# Mainboard.net
KiCad netlist of a schematic drawn in EAGLE
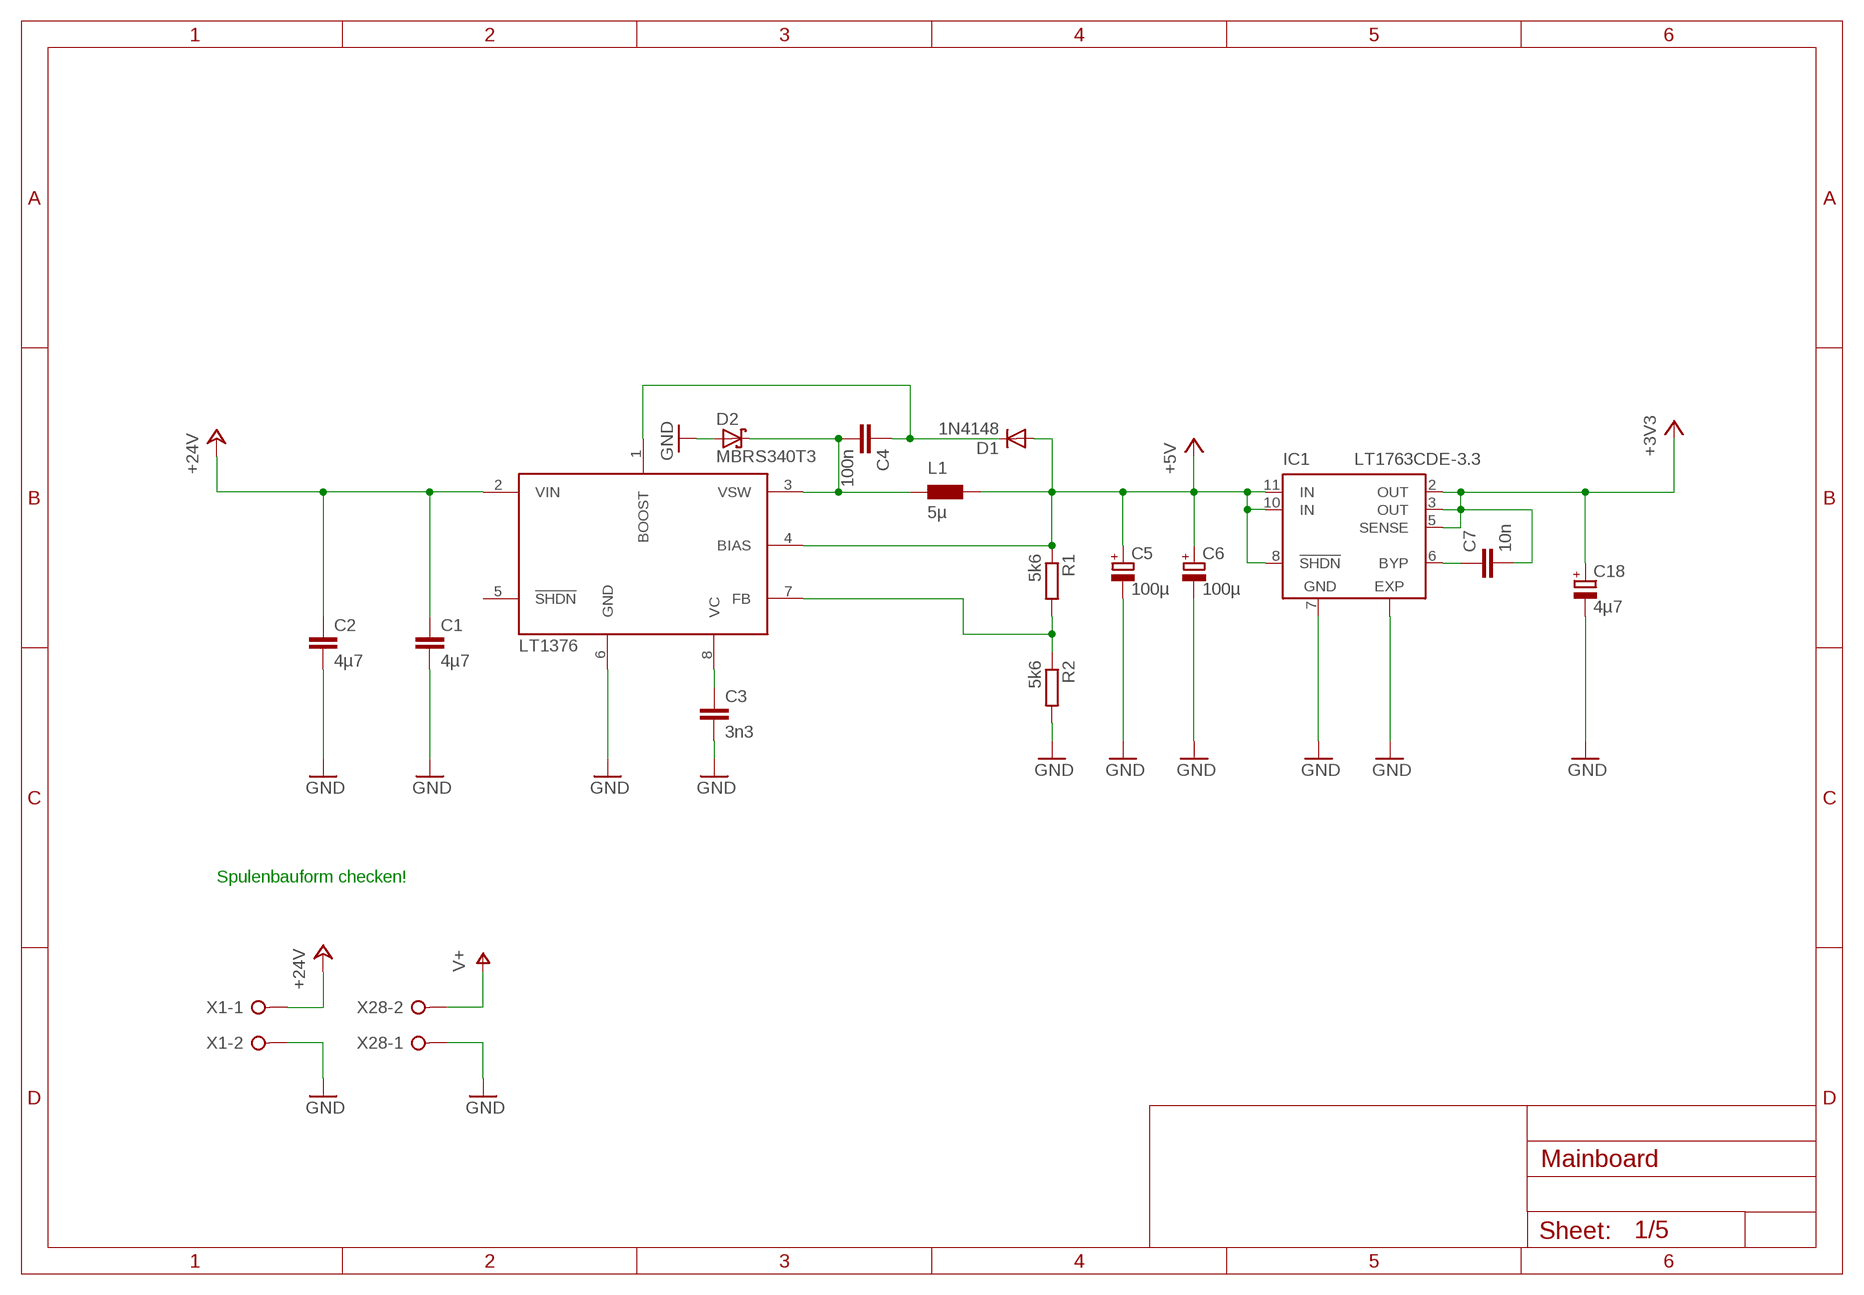
[diagram p0: schematic, sheet 1]
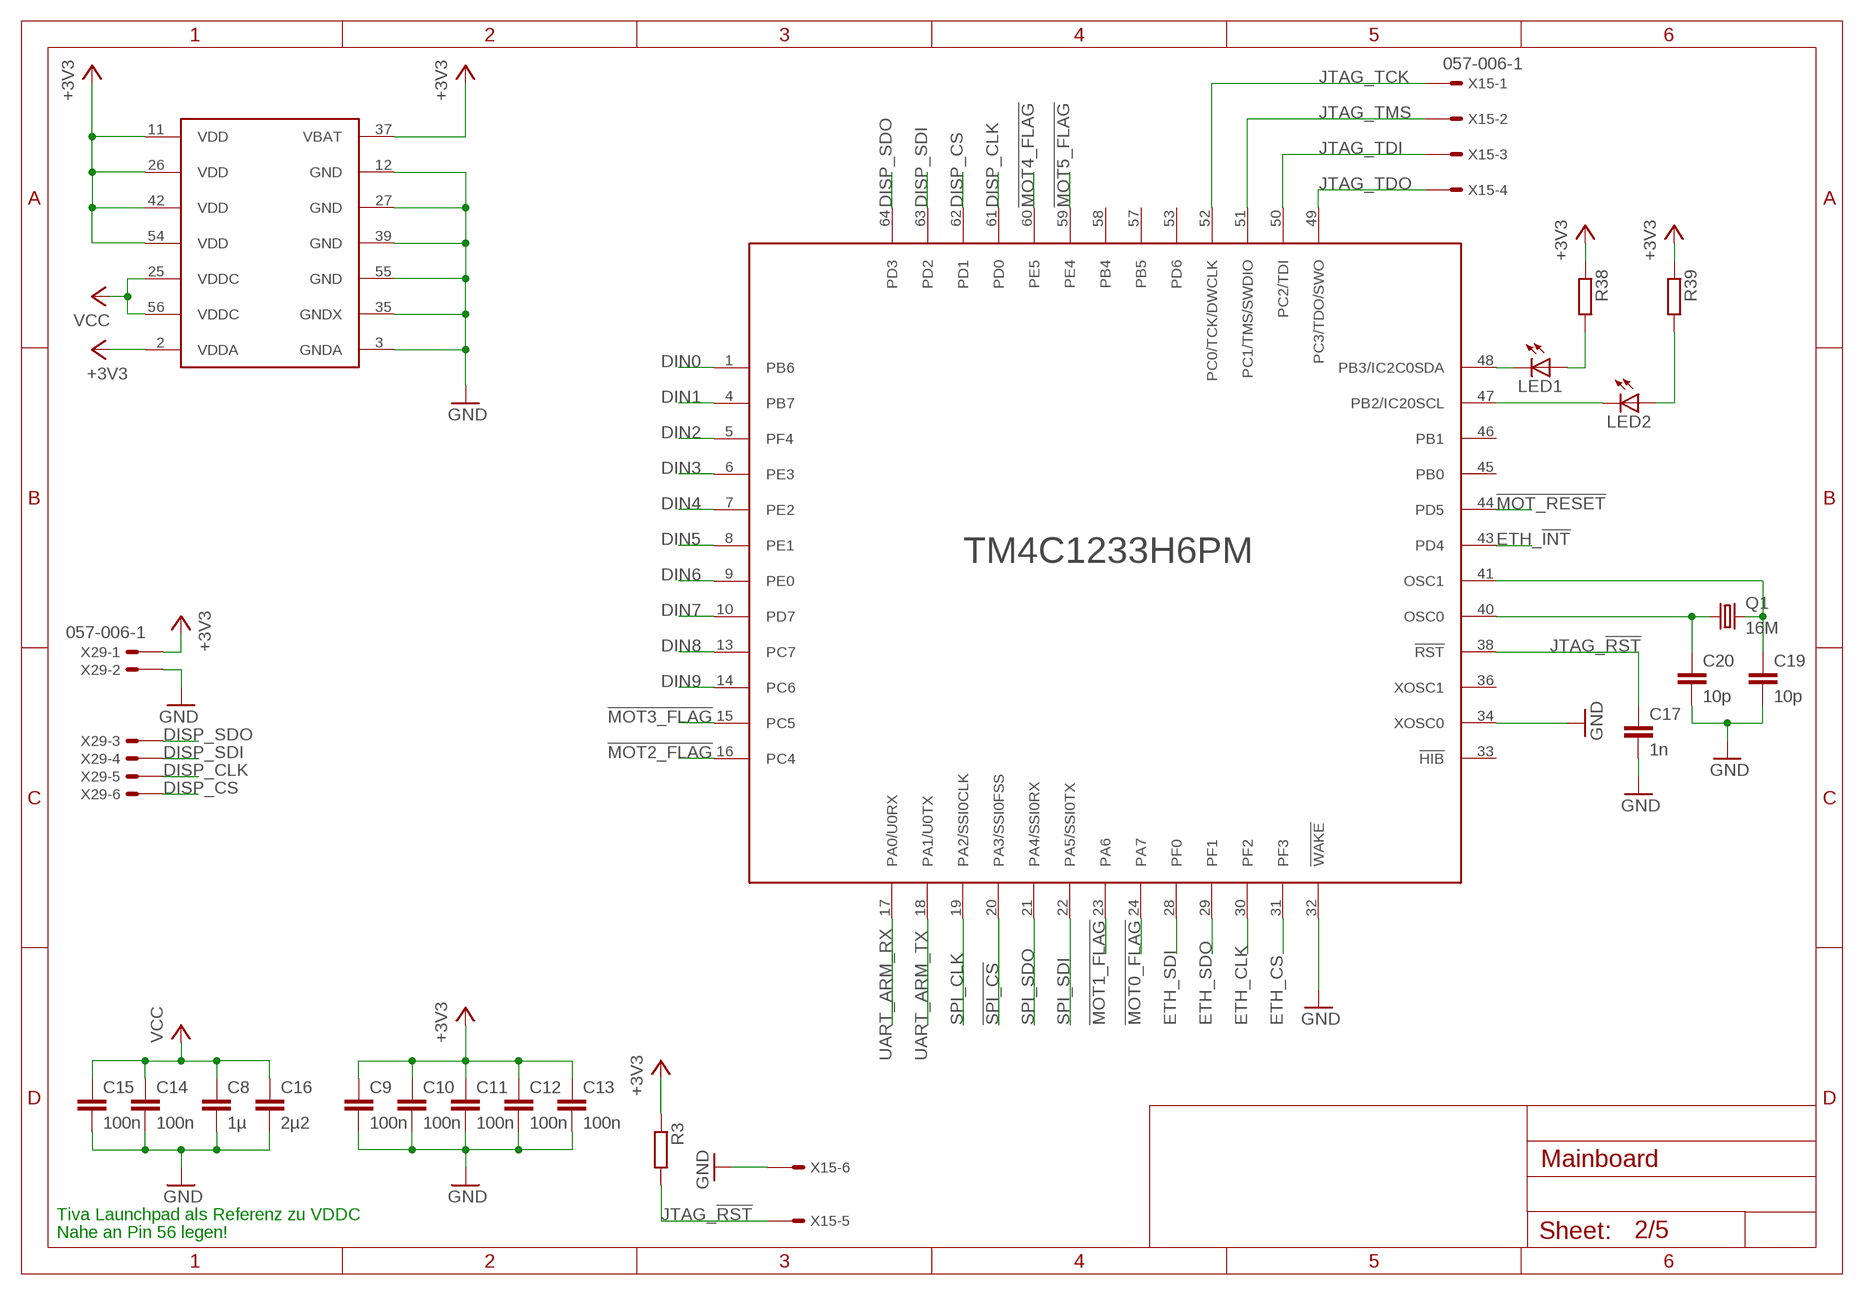
[diagram p1: schematic, sheet 2]
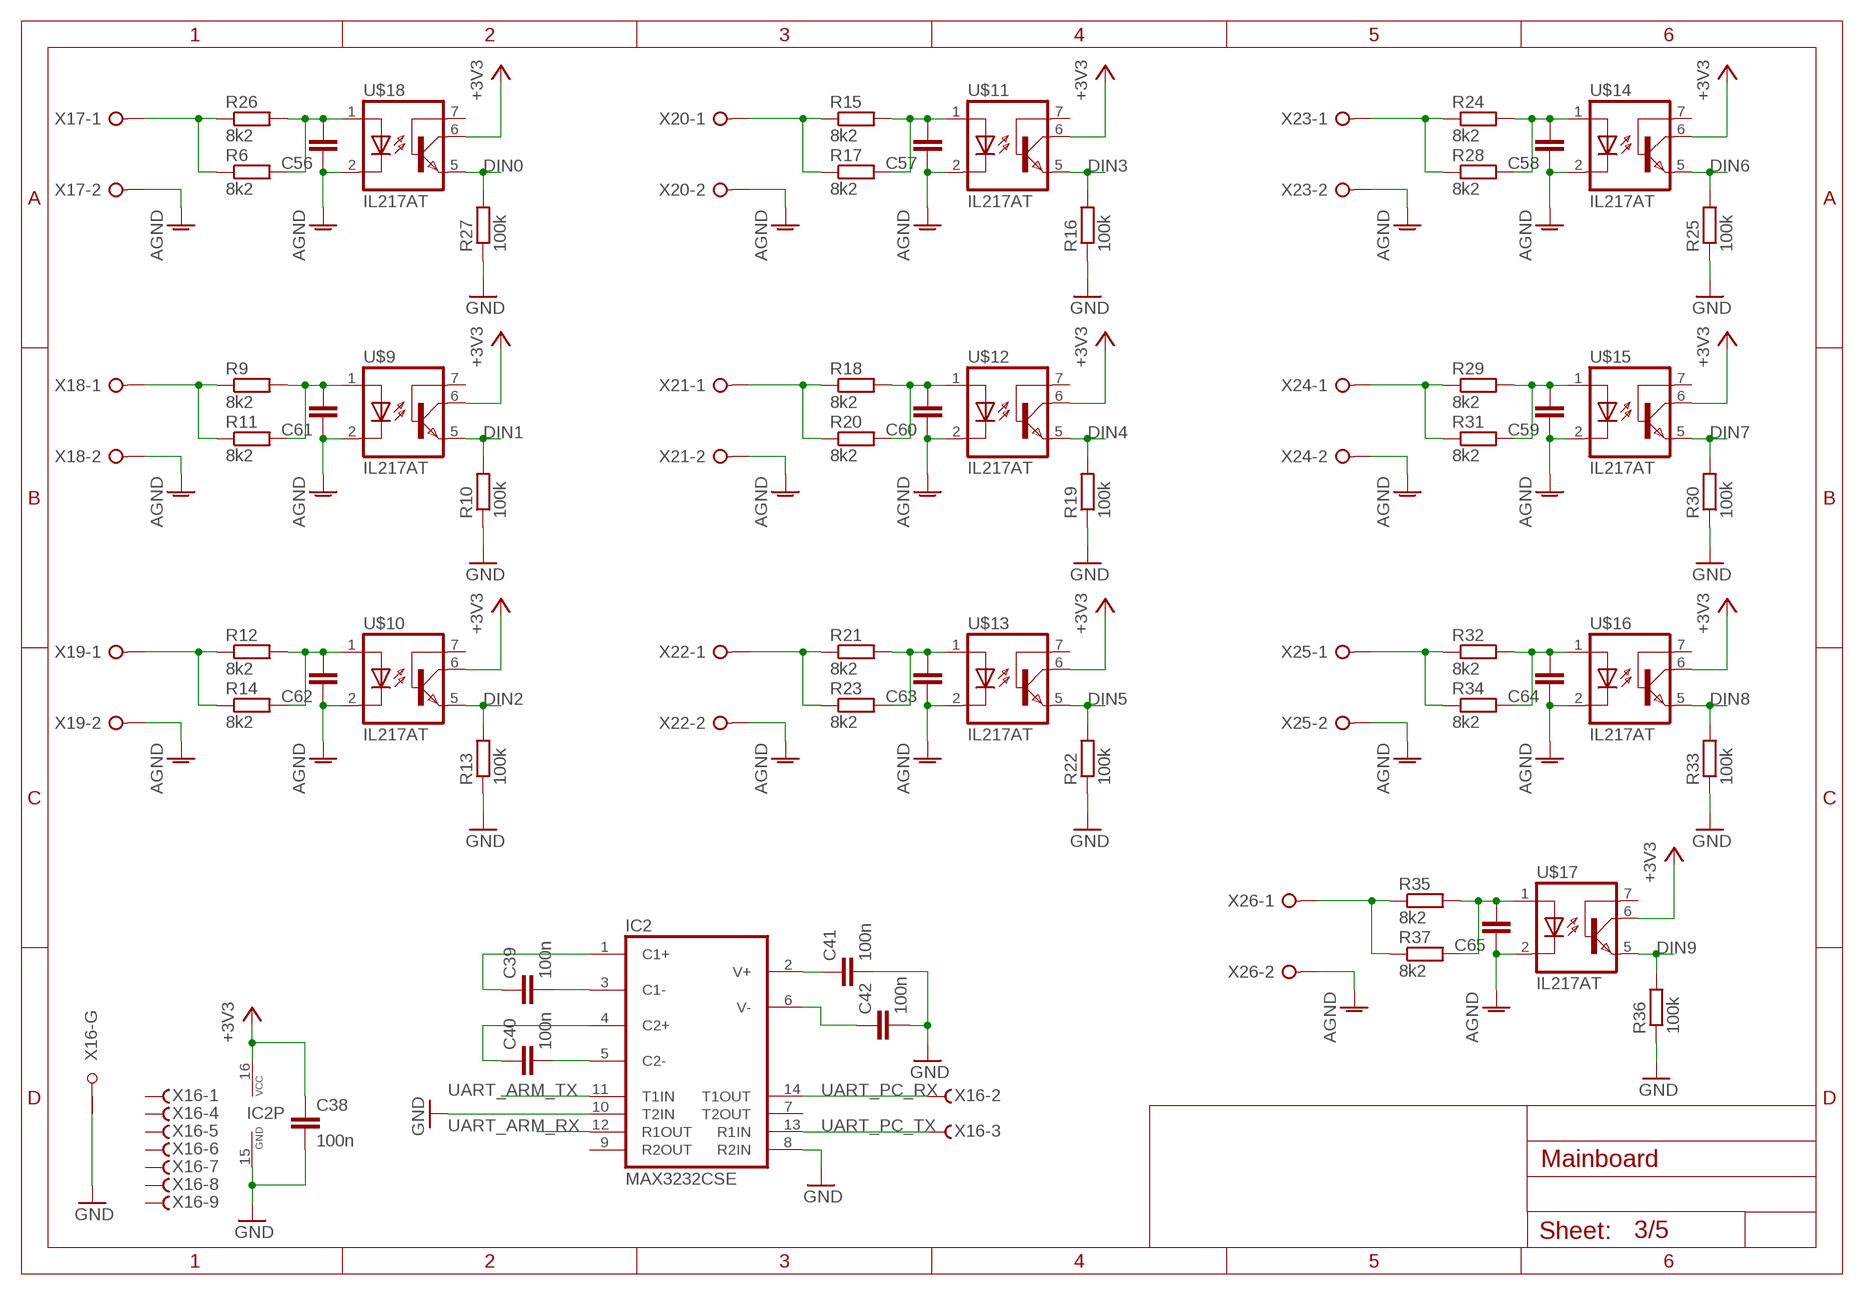
[diagram p2: schematic, sheet 3]
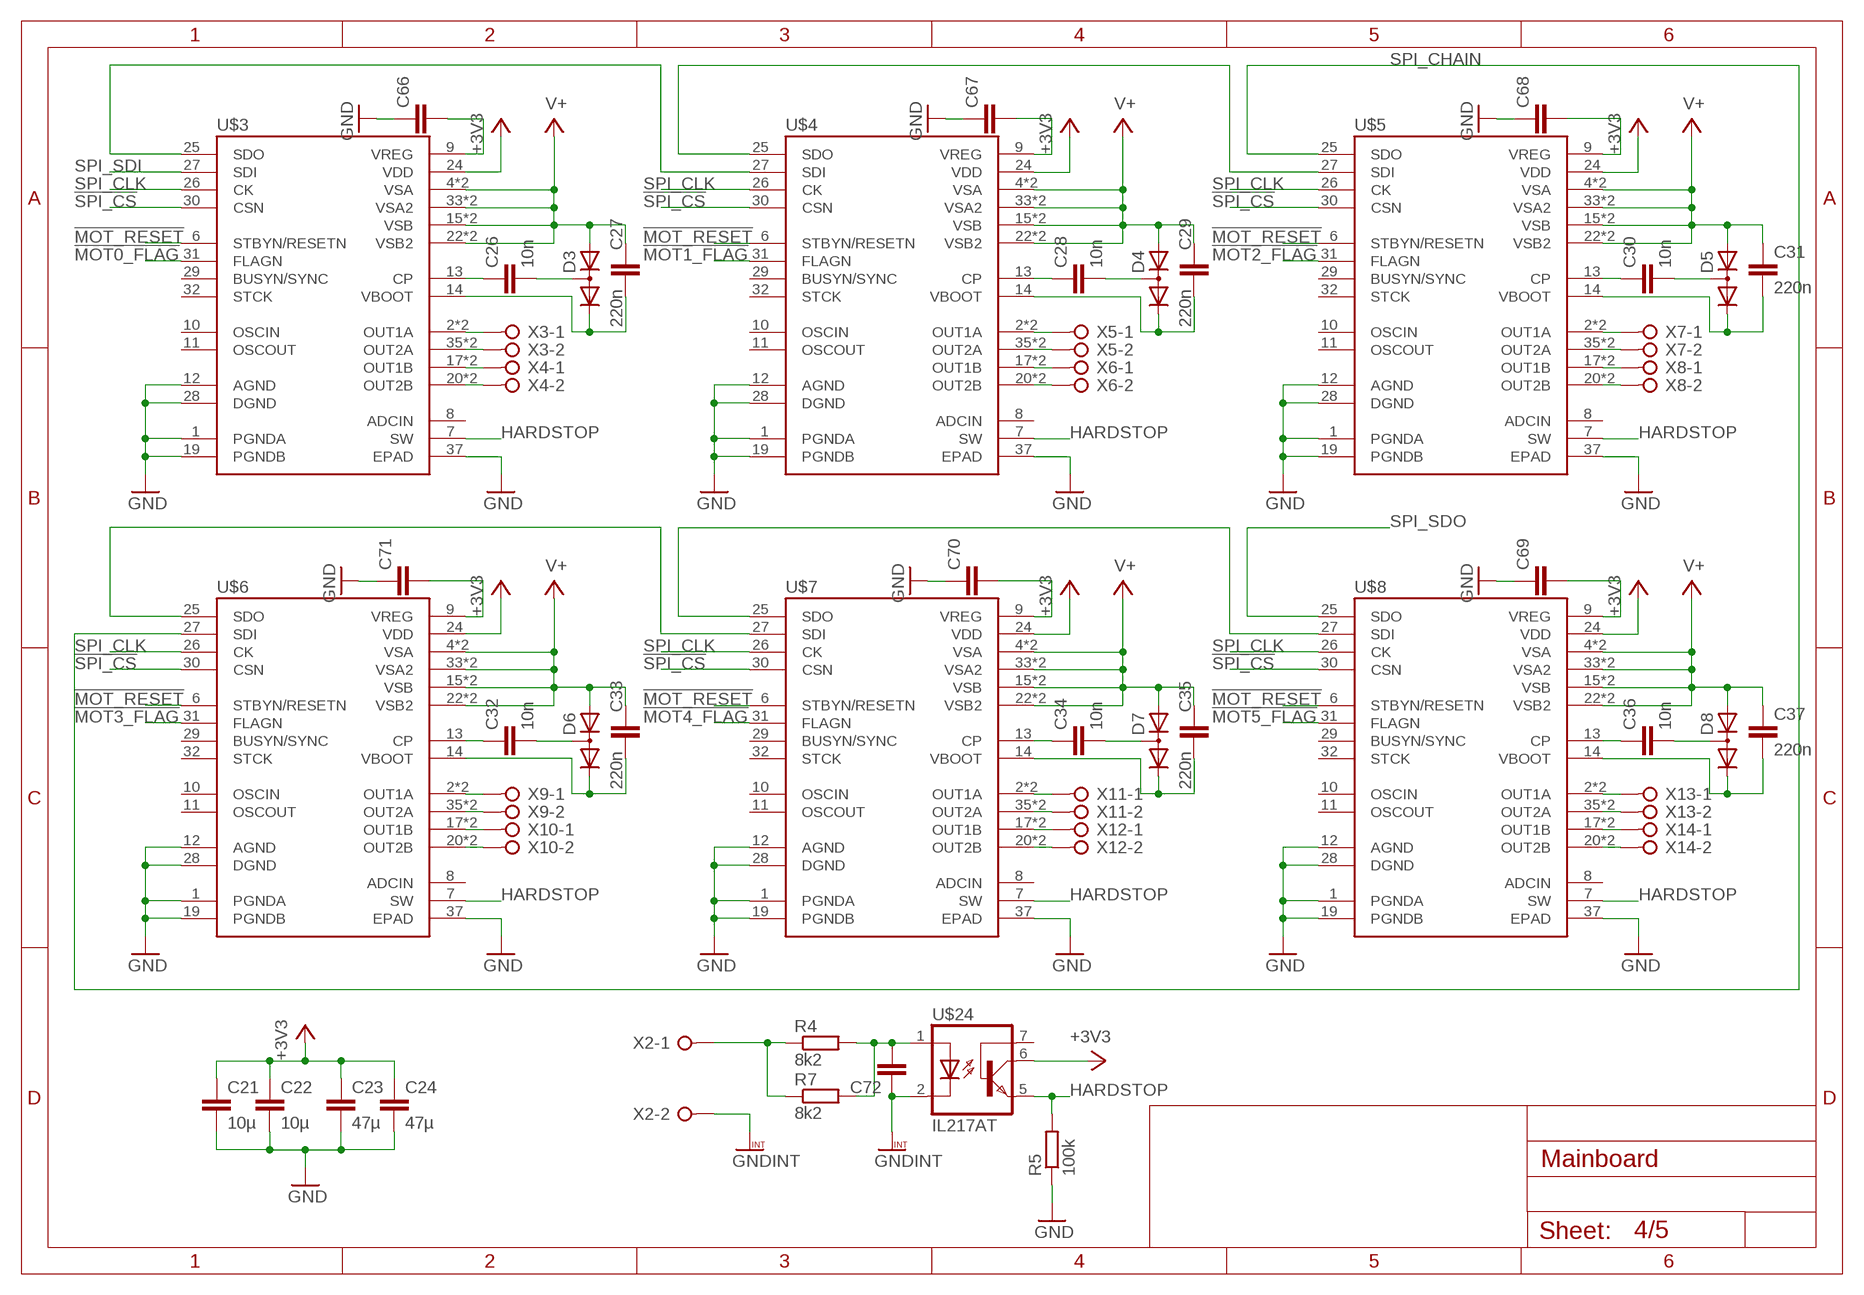
[diagram p3: schematic, sheet 4]
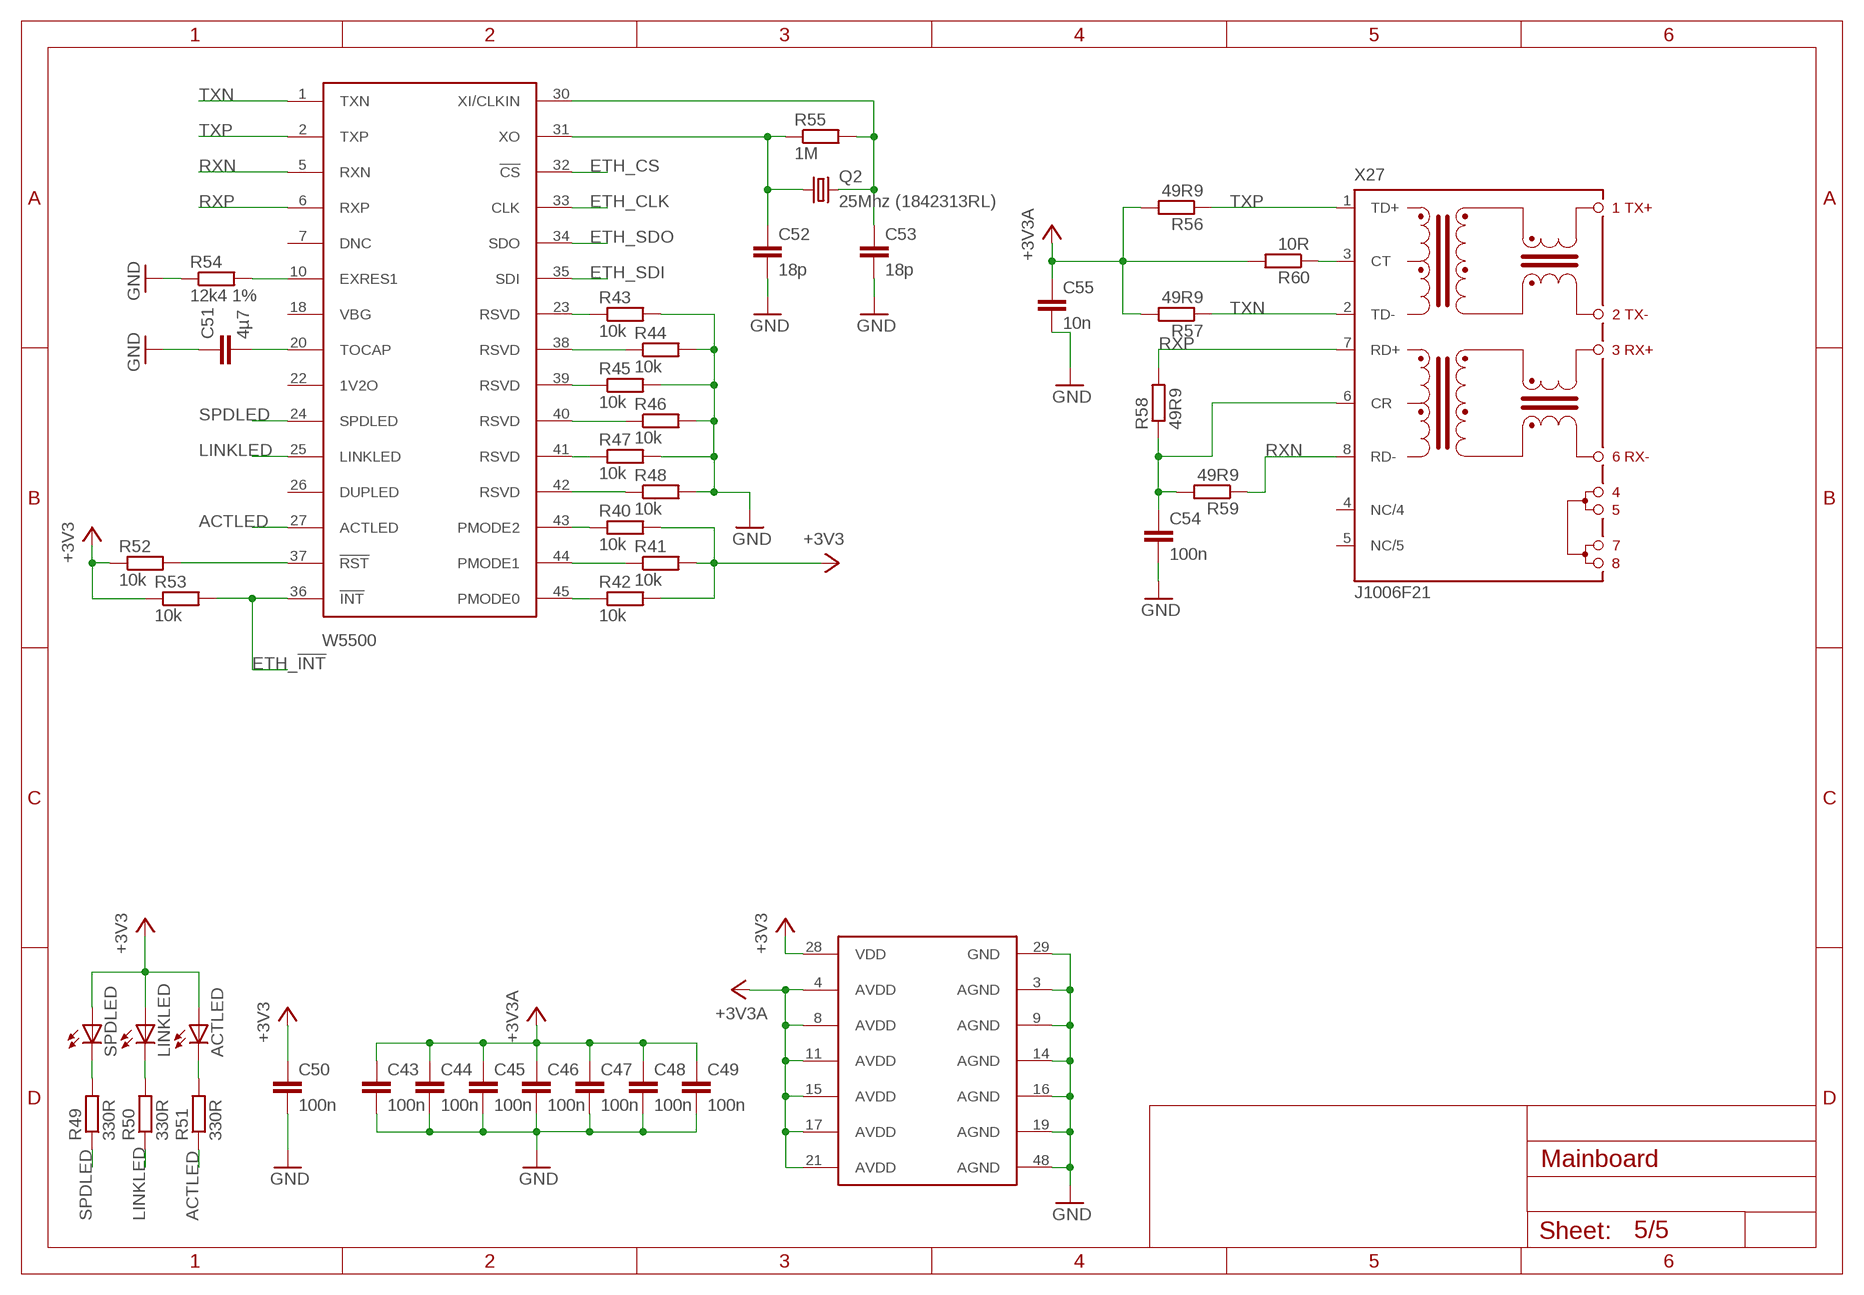
[diagram p4: schematic, sheet 5]

(export (version "E")
  (design (tool "Eeschema 10.0.6"))
  (components
    (comp (ref "ACTLED")
      (value "LEDCHIPLED_0805")
      (footprint "eagle-import:CHIPLED_0805")
      (libsource (lib "eagle-import") (part "LEDCHIPLED_0805"))
    )
    (comp (ref "C43")
      (value "100n")
      (footprint "eagle-import:C0805")
      (libsource (lib "eagle-import") (part "C-EUC0805"))
    )
    (comp (ref "C44")
      (value "100n")
      (footprint "eagle-import:C0805")
      (libsource (lib "eagle-import") (part "C-EUC0805"))
    )
    (comp (ref "C45")
      (value "100n")
      (footprint "eagle-import:C0805")
      (libsource (lib "eagle-import") (part "C-EUC0805"))
    )
    (comp (ref "C46")
      (value "100n")
      (footprint "eagle-import:C0805")
      (libsource (lib "eagle-import") (part "C-EUC0805"))
    )
    (comp (ref "C47")
      (value "100n")
      (footprint "eagle-import:C0805")
      (libsource (lib "eagle-import") (part "C-EUC0805"))
    )
    (comp (ref "C48")
      (value "100n")
      (footprint "eagle-import:C0805")
      (libsource (lib "eagle-import") (part "C-EUC0805"))
    )
    (comp (ref "C49")
      (value "100n")
      (footprint "eagle-import:C0805")
      (libsource (lib "eagle-import") (part "C-EUC0805"))
    )
    (comp (ref "C50")
      (value "100n")
      (footprint "eagle-import:C0805")
      (libsource (lib "eagle-import") (part "C-EUC0805"))
    )
    (comp (ref "C51")
      (value "4µ7")
      (footprint "eagle-import:C0805")
      (libsource (lib "eagle-import") (part "C-EUC0805"))
    )
    (comp (ref "C52")
      (value "18p")
      (footprint "eagle-import:C0805")
      (libsource (lib "eagle-import") (part "C-EUC0805"))
    )
    (comp (ref "C53")
      (value "18p")
      (footprint "eagle-import:C0805")
      (libsource (lib "eagle-import") (part "C-EUC0805"))
    )
    (comp (ref "C54")
      (value "100n")
      (footprint "eagle-import:C0805")
      (libsource (lib "eagle-import") (part "C-EUC0805"))
    )
    (comp (ref "C55")
      (value "10n")
      (footprint "eagle-import:C0805")
      (libsource (lib "eagle-import") (part "C-EUC0805"))
    )
    (comp (ref "LINKLED")
      (value "LEDCHIPLED_0805")
      (footprint "eagle-import:CHIPLED_0805")
      (libsource (lib "eagle-import") (part "LEDCHIPLED_0805"))
    )
    (comp (ref "Q2")
      (value "25Mhz (1842313RL)")
      (footprint "eagle-import:HC49UP")
      (libsource (lib "eagle-import") (part "CRYSTALHC49UP"))
    )
    (comp (ref "R40")
      (value "10k")
      (footprint "eagle-import:R0805")
      (libsource (lib "eagle-import") (part "R-EU_R0805"))
    )
    (comp (ref "R41")
      (value "10k")
      (footprint "eagle-import:R0805")
      (libsource (lib "eagle-import") (part "R-EU_R0805"))
    )
    (comp (ref "R42")
      (value "10k")
      (footprint "eagle-import:R0805")
      (libsource (lib "eagle-import") (part "R-EU_R0805"))
    )
    (comp (ref "R43")
      (value "10k")
      (footprint "eagle-import:R0805")
      (libsource (lib "eagle-import") (part "R-EU_R0805"))
    )
    (comp (ref "R44")
      (value "10k")
      (footprint "eagle-import:R0805")
      (libsource (lib "eagle-import") (part "R-EU_R0805"))
    )
    (comp (ref "R45")
      (value "10k")
      (footprint "eagle-import:R0805")
      (libsource (lib "eagle-import") (part "R-EU_R0805"))
    )
    (comp (ref "R46")
      (value "10k")
      (footprint "eagle-import:R0805")
      (libsource (lib "eagle-import") (part "R-EU_R0805"))
    )
    (comp (ref "R47")
      (value "10k")
      (footprint "eagle-import:R0805")
      (libsource (lib "eagle-import") (part "R-EU_R0805"))
    )
    (comp (ref "R48")
      (value "10k")
      (footprint "eagle-import:R0805")
      (libsource (lib "eagle-import") (part "R-EU_R0805"))
    )
    (comp (ref "R49")
      (value "330R")
      (footprint "eagle-import:R0805")
      (libsource (lib "eagle-import") (part "R-EU_R0805"))
    )
    (comp (ref "R50")
      (value "330R")
      (footprint "eagle-import:R0805")
      (libsource (lib "eagle-import") (part "R-EU_R0805"))
    )
    (comp (ref "R51")
      (value "330R")
      (footprint "eagle-import:R0805")
      (libsource (lib "eagle-import") (part "R-EU_R0805"))
    )
    (comp (ref "R52")
      (value "10k")
      (footprint "eagle-import:R0805")
      (libsource (lib "eagle-import") (part "R-EU_R0805"))
    )
    (comp (ref "R53")
      (value "10k")
      (footprint "eagle-import:R0805")
      (libsource (lib "eagle-import") (part "R-EU_R0805"))
    )
    (comp (ref "R54")
      (value "12k4 1%")
      (footprint "eagle-import:R0805")
      (libsource (lib "eagle-import") (part "R-EU_R0805"))
    )
    (comp (ref "R55")
      (value "1M")
      (footprint "eagle-import:R0805")
      (libsource (lib "eagle-import") (part "R-EU_R0805"))
    )
    (comp (ref "R56")
      (value "49R9")
      (footprint "eagle-import:R0805")
      (libsource (lib "eagle-import") (part "R-EU_R0805"))
    )
    (comp (ref "R57")
      (value "49R9")
      (footprint "eagle-import:R0805")
      (libsource (lib "eagle-import") (part "R-EU_R0805"))
    )
    (comp (ref "R58")
      (value "49R9")
      (footprint "eagle-import:R0805")
      (libsource (lib "eagle-import") (part "R-EU_R0805"))
    )
    (comp (ref "R59")
      (value "49R9")
      (footprint "eagle-import:R0805")
      (libsource (lib "eagle-import") (part "R-EU_R0805"))
    )
    (comp (ref "R60")
      (value "10R")
      (footprint "eagle-import:R0805")
      (libsource (lib "eagle-import") (part "R-EU_R0805"))
    )
    (comp (ref "SPDLED")
      (value "LEDCHIPLED_0805")
      (footprint "eagle-import:CHIPLED_0805")
      (libsource (lib "eagle-import") (part "LEDCHIPLED_0805"))
    )
    (comp (ref "U$19")
      (value "W5500")
      (footprint "eagle-import:LQFP48")
      (libsource (lib "eagle-import") (part "W5500"))
    )
    (comp (ref "X27")
      (value "J1006F21")
      (footprint "eagle-import:J1")
      (libsource (lib "eagle-import") (part "J1006F21"))
    )
    (comp (ref "C21")
      (value "10µ")
      (footprint "eagle-import:C0805")
      (libsource (lib "eagle-import") (part "C-EUC0805"))
    )
    (comp (ref "C22")
      (value "10µ")
      (footprint "eagle-import:C0805")
      (libsource (lib "eagle-import") (part "C-EUC0805"))
    )
    (comp (ref "C23")
      (value "47µ")
      (footprint "eagle-import:C0805")
      (libsource (lib "eagle-import") (part "C-EUC0805"))
    )
    (comp (ref "C24")
      (value "47µ")
      (footprint "eagle-import:C0805")
      (libsource (lib "eagle-import") (part "C-EUC0805"))
    )
    (comp (ref "C26")
      (value "10n")
      (footprint "eagle-import:C0805")
      (libsource (lib "eagle-import") (part "C-EUC0805"))
    )
    (comp (ref "C27")
      (value "220n")
      (footprint "eagle-import:C0805")
      (libsource (lib "eagle-import") (part "C-EUC0805"))
    )
    (comp (ref "C28")
      (value "10n")
      (footprint "eagle-import:C0805")
      (libsource (lib "eagle-import") (part "C-EUC0805"))
    )
    (comp (ref "C29")
      (value "220n")
      (footprint "eagle-import:C0805")
      (libsource (lib "eagle-import") (part "C-EUC0805"))
    )
    (comp (ref "C30")
      (value "10n")
      (footprint "eagle-import:C0805")
      (libsource (lib "eagle-import") (part "C-EUC0805"))
    )
    (comp (ref "C31")
      (value "220n")
      (footprint "eagle-import:C0805")
      (libsource (lib "eagle-import") (part "C-EUC0805"))
    )
    (comp (ref "C32")
      (value "10n")
      (footprint "eagle-import:C0805")
      (libsource (lib "eagle-import") (part "C-EUC0805"))
    )
    (comp (ref "C33")
      (value "220n")
      (footprint "eagle-import:C0805")
      (libsource (lib "eagle-import") (part "C-EUC0805"))
    )
    (comp (ref "C34")
      (value "10n")
      (footprint "eagle-import:C0805")
      (libsource (lib "eagle-import") (part "C-EUC0805"))
    )
    (comp (ref "C35")
      (value "220n")
      (footprint "eagle-import:C0805")
      (libsource (lib "eagle-import") (part "C-EUC0805"))
    )
    (comp (ref "C36")
      (value "10n")
      (footprint "eagle-import:C0805")
      (libsource (lib "eagle-import") (part "C-EUC0805"))
    )
    (comp (ref "C37")
      (value "220n")
      (footprint "eagle-import:C0805")
      (libsource (lib "eagle-import") (part "C-EUC0805"))
    )
    (comp (ref "C66")
      (value "C-EUC1210")
      (footprint "eagle-import:C1210")
      (libsource (lib "eagle-import") (part "C-EUC1210"))
    )
    (comp (ref "C67")
      (value "C-EUC1210")
      (footprint "eagle-import:C1210")
      (libsource (lib "eagle-import") (part "C-EUC1210"))
    )
    (comp (ref "C68")
      (value "C-EUC1210")
      (footprint "eagle-import:C1210")
      (libsource (lib "eagle-import") (part "C-EUC1210"))
    )
    (comp (ref "C69")
      (value "C-EUC1210")
      (footprint "eagle-import:C1210")
      (libsource (lib "eagle-import") (part "C-EUC1210"))
    )
    (comp (ref "C70")
      (value "C-EUC1210")
      (footprint "eagle-import:C1210")
      (libsource (lib "eagle-import") (part "C-EUC1210"))
    )
    (comp (ref "C71")
      (value "C-EUC1210")
      (footprint "eagle-import:C1210")
      (libsource (lib "eagle-import") (part "C-EUC1210"))
    )
    (comp (ref "C72")
      (value "C-EUC1210")
      (footprint "eagle-import:C1210")
      (libsource (lib "eagle-import") (part "C-EUC1210"))
    )
    (comp (ref "D3")
      (value "HSMS-2802-TR1G")
      (footprint "eagle-import:SOT23")
      (libsource (lib "eagle-import") (part "DIODE_2CACA-SOT23"))
    )
    (comp (ref "D4")
      (value "HSMS-2802-TR1G")
      (footprint "eagle-import:SOT23")
      (libsource (lib "eagle-import") (part "DIODE_2CACA-SOT23"))
    )
    (comp (ref "D5")
      (value "HSMS-2802-TR1G")
      (footprint "eagle-import:SOT23")
      (libsource (lib "eagle-import") (part "DIODE_2CACA-SOT23"))
    )
    (comp (ref "D6")
      (value "HSMS-2802-TR1G")
      (footprint "eagle-import:SOT23")
      (libsource (lib "eagle-import") (part "DIODE_2CACA-SOT23"))
    )
    (comp (ref "D7")
      (value "HSMS-2802-TR1G")
      (footprint "eagle-import:SOT23")
      (libsource (lib "eagle-import") (part "DIODE_2CACA-SOT23"))
    )
    (comp (ref "D8")
      (value "HSMS-2802-TR1G")
      (footprint "eagle-import:SOT23")
      (libsource (lib "eagle-import") (part "DIODE_2CACA-SOT23"))
    )
    (comp (ref "R4")
      (value "8k2")
      (footprint "eagle-import:R0805")
      (libsource (lib "eagle-import") (part "R-EU_R0805"))
    )
    (comp (ref "R5")
      (value "100k")
      (footprint "eagle-import:R0805")
      (libsource (lib "eagle-import") (part "R-EU_R0805"))
    )
    (comp (ref "R7")
      (value "8k2")
      (footprint "eagle-import:R0805")
      (libsource (lib "eagle-import") (part "R-EU_R0805"))
    )
    (comp (ref "U$3")
      (value "L6470HPOWERSO36")
      (footprint "eagle-import:SOP65P1400X360-37N")
      (libsource (lib "eagle-import") (part "L6470HPOWERSO36"))
    )
    (comp (ref "U$4")
      (value "L6470HPOWERSO36")
      (footprint "eagle-import:SOP65P1400X360-37N")
      (libsource (lib "eagle-import") (part "L6470HPOWERSO36"))
    )
    (comp (ref "U$5")
      (value "L6470HPOWERSO36")
      (footprint "eagle-import:SOP65P1400X360-37N")
      (libsource (lib "eagle-import") (part "L6470HPOWERSO36"))
    )
    (comp (ref "U$6")
      (value "L6470HPOWERSO36")
      (footprint "eagle-import:SOP65P1400X360-37N")
      (libsource (lib "eagle-import") (part "L6470HPOWERSO36"))
    )
    (comp (ref "U$7")
      (value "L6470HPOWERSO36")
      (footprint "eagle-import:SOP65P1400X360-37N")
      (libsource (lib "eagle-import") (part "L6470HPOWERSO36"))
    )
    (comp (ref "U$8")
      (value "L6470HPOWERSO36")
      (footprint "eagle-import:SOP65P1400X360-37N")
      (libsource (lib "eagle-import") (part "L6470HPOWERSO36"))
    )
    (comp (ref "U$24")
      (value "IL217AT")
      (footprint "eagle-import:SOIC8")
      (libsource (lib "eagle-import") (part "IL217AT"))
    )
    (comp (ref "X2")
      (value "W237-02P")
      (footprint "eagle-import:W237-132")
      (libsource (lib "eagle-import") (part "W237-02P"))
    )
    (comp (ref "X3")
      (value "W237-02P")
      (footprint "eagle-import:W237-132")
      (libsource (lib "eagle-import") (part "W237-02P"))
    )
    (comp (ref "X4")
      (value "W237-02P")
      (footprint "eagle-import:W237-132")
      (libsource (lib "eagle-import") (part "W237-02P"))
    )
    (comp (ref "X5")
      (value "W237-02P")
      (footprint "eagle-import:W237-132")
      (libsource (lib "eagle-import") (part "W237-02P"))
    )
    (comp (ref "X6")
      (value "W237-02P")
      (footprint "eagle-import:W237-132")
      (libsource (lib "eagle-import") (part "W237-02P"))
    )
    (comp (ref "X7")
      (value "W237-02P")
      (footprint "eagle-import:W237-132")
      (libsource (lib "eagle-import") (part "W237-02P"))
    )
    (comp (ref "X8")
      (value "W237-02P")
      (footprint "eagle-import:W237-132")
      (libsource (lib "eagle-import") (part "W237-02P"))
    )
    (comp (ref "X9")
      (value "W237-02P")
      (footprint "eagle-import:W237-132")
      (libsource (lib "eagle-import") (part "W237-02P"))
    )
    (comp (ref "X10")
      (value "W237-02P")
      (footprint "eagle-import:W237-132")
      (libsource (lib "eagle-import") (part "W237-02P"))
    )
    (comp (ref "X11")
      (value "W237-02P")
      (footprint "eagle-import:W237-132")
      (libsource (lib "eagle-import") (part "W237-02P"))
    )
    (comp (ref "X12")
      (value "W237-02P")
      (footprint "eagle-import:W237-132")
      (libsource (lib "eagle-import") (part "W237-02P"))
    )
    (comp (ref "X13")
      (value "W237-02P")
      (footprint "eagle-import:W237-132")
      (libsource (lib "eagle-import") (part "W237-02P"))
    )
    (comp (ref "X14")
      (value "W237-02P")
      (footprint "eagle-import:W237-132")
      (libsource (lib "eagle-import") (part "W237-02P"))
    )
    (comp (ref "C1")
      (value "4µ7")
      (footprint "eagle-import:C0805")
      (libsource (lib "eagle-import") (part "C-EUC0805"))
    )
    (comp (ref "C2")
      (value "4µ7")
      (footprint "eagle-import:C0805")
      (libsource (lib "eagle-import") (part "C-EUC0805"))
    )
    (comp (ref "C3")
      (value "3n3")
      (footprint "eagle-import:C0805")
      (libsource (lib "eagle-import") (part "C-EUC0805"))
    )
    (comp (ref "C4")
      (value "100n")
      (footprint "eagle-import:C0805")
      (libsource (lib "eagle-import") (part "C-EUC0805"))
    )
    (comp (ref "C5")
      (value "100µ")
      (footprint "eagle-import:UD-6,3X7,7_NICHICON")
      (libsource (lib "eagle-import") (part "CPOL-EUUD-6,3X7,7"))
    )
    (comp (ref "C6")
      (value "100µ")
      (footprint "eagle-import:UD-6,3X7,7_NICHICON")
      (libsource (lib "eagle-import") (part "CPOL-EUUD-6,3X7,7"))
    )
    (comp (ref "C7")
      (value "10n")
      (footprint "eagle-import:C0805")
      (libsource (lib "eagle-import") (part "C-EUC0805"))
    )
    (comp (ref "C18")
      (value "4µ7")
      (footprint "eagle-import:UD-6,3X7,7_NICHICON")
      (libsource (lib "eagle-import") (part "CPOL-EUUD-6,3X7,7"))
    )
    (comp (ref "D1")
      (value "1N4148")
      (footprint "eagle-import:SOD123")
      (libsource (lib "eagle-import") (part "DIODE-SOD123"))
    )
    (comp (ref "D2")
      (value "MBRS340T3")
      (footprint "eagle-import:SMC")
      (libsource (lib "eagle-import") (part "MBRS30T34"))
    )
    (comp (ref "IC1")
      (value "LT1763CDE-3.3")
      (footprint "eagle-import:DFN12")
      (libsource (lib "eagle-import") (part "LT1763CDE-3.3"))
    )
    (comp (ref "L1")
      (value "5µ")
      (footprint "eagle-import:PIS4720")
      (libsource (lib "eagle-import") (part "PIS4720"))
    )
    (comp (ref "R1")
      (value "5k6")
      (footprint "eagle-import:R0805")
      (libsource (lib "eagle-import") (part "R-EU_R0805"))
    )
    (comp (ref "R2")
      (value "5k6")
      (footprint "eagle-import:R0805")
      (libsource (lib "eagle-import") (part "R-EU_R0805"))
    )
    (comp (ref "U$1")
      (value "LT1376")
      (footprint "eagle-import:SOIC8")
      (libsource (lib "eagle-import") (part "LT1376"))
    )
    (comp (ref "X1")
      (value "W237-02P")
      (footprint "eagle-import:W237-132")
      (libsource (lib "eagle-import") (part "W237-02P"))
    )
    (comp (ref "X28")
      (value "W237-02P")
      (footprint "eagle-import:W237-132")
      (fields (field (name "OC_FARNELL") "unknown") (field (name "OC_NEWARK") "unknown"))
      (libsource (lib "eagle-import") (part "W237-02P"))
    )
    (comp (ref "C38")
      (value "100n")
      (footprint "eagle-import:C0805")
      (libsource (lib "eagle-import") (part "C-EUC0805"))
    )
    (comp (ref "C39")
      (value "100n")
      (footprint "eagle-import:C0805")
      (libsource (lib "eagle-import") (part "C-EUC0805"))
    )
    (comp (ref "C40")
      (value "100n")
      (footprint "eagle-import:C0805")
      (libsource (lib "eagle-import") (part "C-EUC0805"))
    )
    (comp (ref "C41")
      (value "100n")
      (footprint "eagle-import:C0805")
      (libsource (lib "eagle-import") (part "C-EUC0805"))
    )
    (comp (ref "C42")
      (value "100n")
      (footprint "eagle-import:C0805")
      (libsource (lib "eagle-import") (part "C-EUC0805"))
    )
    (comp (ref "C56")
      (value "C-EUC1210")
      (footprint "eagle-import:C1210")
      (libsource (lib "eagle-import") (part "C-EUC1210"))
    )
    (comp (ref "C57")
      (value "C-EUC1210")
      (footprint "eagle-import:C1210")
      (libsource (lib "eagle-import") (part "C-EUC1210"))
    )
    (comp (ref "C58")
      (value "C-EUC1210")
      (footprint "eagle-import:C1210")
      (libsource (lib "eagle-import") (part "C-EUC1210"))
    )
    (comp (ref "C59")
      (value "C-EUC1210")
      (footprint "eagle-import:C1210")
      (libsource (lib "eagle-import") (part "C-EUC1210"))
    )
    (comp (ref "C60")
      (value "C-EUC1210")
      (footprint "eagle-import:C1210")
      (libsource (lib "eagle-import") (part "C-EUC1210"))
    )
    (comp (ref "C61")
      (value "C-EUC1210")
      (footprint "eagle-import:C1210")
      (libsource (lib "eagle-import") (part "C-EUC1210"))
    )
    (comp (ref "C62")
      (value "C-EUC1210")
      (footprint "eagle-import:C1210")
      (libsource (lib "eagle-import") (part "C-EUC1210"))
    )
    (comp (ref "C63")
      (value "C-EUC1210")
      (footprint "eagle-import:C1210")
      (libsource (lib "eagle-import") (part "C-EUC1210"))
    )
    (comp (ref "C64")
      (value "C-EUC1210")
      (footprint "eagle-import:C1210")
      (libsource (lib "eagle-import") (part "C-EUC1210"))
    )
    (comp (ref "C65")
      (value "C-EUC1210")
      (footprint "eagle-import:C1210")
      (libsource (lib "eagle-import") (part "C-EUC1210"))
    )
    (comp (ref "IC2")
      (value "MAX3232CSE")
      (footprint "eagle-import:SO16")
      (libsource (lib "eagle-import") (part "MAX3232SEC"))
    )
    (comp (ref "R6")
      (value "8k2")
      (footprint "eagle-import:R0805")
      (libsource (lib "eagle-import") (part "R-EU_R0805"))
    )
    (comp (ref "R9")
      (value "8k2")
      (footprint "eagle-import:R0805")
      (libsource (lib "eagle-import") (part "R-EU_R0805"))
    )
    (comp (ref "R10")
      (value "100k")
      (footprint "eagle-import:R0805")
      (libsource (lib "eagle-import") (part "R-EU_R0805"))
    )
    (comp (ref "R11")
      (value "8k2")
      (footprint "eagle-import:R0805")
      (libsource (lib "eagle-import") (part "R-EU_R0805"))
    )
    (comp (ref "R12")
      (value "8k2")
      (footprint "eagle-import:R0805")
      (libsource (lib "eagle-import") (part "R-EU_R0805"))
    )
    (comp (ref "R13")
      (value "100k")
      (footprint "eagle-import:R0805")
      (libsource (lib "eagle-import") (part "R-EU_R0805"))
    )
    (comp (ref "R14")
      (value "8k2")
      (footprint "eagle-import:R0805")
      (libsource (lib "eagle-import") (part "R-EU_R0805"))
    )
    (comp (ref "R15")
      (value "8k2")
      (footprint "eagle-import:R0805")
      (libsource (lib "eagle-import") (part "R-EU_R0805"))
    )
    (comp (ref "R16")
      (value "100k")
      (footprint "eagle-import:R0805")
      (libsource (lib "eagle-import") (part "R-EU_R0805"))
    )
    (comp (ref "R17")
      (value "8k2")
      (footprint "eagle-import:R0805")
      (libsource (lib "eagle-import") (part "R-EU_R0805"))
    )
    (comp (ref "R18")
      (value "8k2")
      (footprint "eagle-import:R0805")
      (libsource (lib "eagle-import") (part "R-EU_R0805"))
    )
    (comp (ref "R19")
      (value "100k")
      (footprint "eagle-import:R0805")
      (libsource (lib "eagle-import") (part "R-EU_R0805"))
    )
    (comp (ref "R20")
      (value "8k2")
      (footprint "eagle-import:R0805")
      (libsource (lib "eagle-import") (part "R-EU_R0805"))
    )
    (comp (ref "R21")
      (value "8k2")
      (footprint "eagle-import:R0805")
      (libsource (lib "eagle-import") (part "R-EU_R0805"))
    )
    (comp (ref "R22")
      (value "100k")
      (footprint "eagle-import:R0805")
      (libsource (lib "eagle-import") (part "R-EU_R0805"))
    )
    (comp (ref "R23")
      (value "8k2")
      (footprint "eagle-import:R0805")
      (libsource (lib "eagle-import") (part "R-EU_R0805"))
    )
    (comp (ref "R24")
      (value "8k2")
      (footprint "eagle-import:R0805")
      (libsource (lib "eagle-import") (part "R-EU_R0805"))
    )
    (comp (ref "R25")
      (value "100k")
      (footprint "eagle-import:R0805")
      (libsource (lib "eagle-import") (part "R-EU_R0805"))
    )
    (comp (ref "R26")
      (value "8k2")
      (footprint "eagle-import:R0805")
      (libsource (lib "eagle-import") (part "R-EU_R0805"))
    )
    (comp (ref "R27")
      (value "100k")
      (footprint "eagle-import:R0805")
      (libsource (lib "eagle-import") (part "R-EU_R0805"))
    )
    (comp (ref "R28")
      (value "8k2")
      (footprint "eagle-import:R0805")
      (libsource (lib "eagle-import") (part "R-EU_R0805"))
    )
    (comp (ref "R29")
      (value "8k2")
      (footprint "eagle-import:R0805")
      (libsource (lib "eagle-import") (part "R-EU_R0805"))
    )
    (comp (ref "R30")
      (value "100k")
      (footprint "eagle-import:R0805")
      (libsource (lib "eagle-import") (part "R-EU_R0805"))
    )
    (comp (ref "R31")
      (value "8k2")
      (footprint "eagle-import:R0805")
      (libsource (lib "eagle-import") (part "R-EU_R0805"))
    )
    (comp (ref "R32")
      (value "8k2")
      (footprint "eagle-import:R0805")
      (libsource (lib "eagle-import") (part "R-EU_R0805"))
    )
    (comp (ref "R33")
      (value "100k")
      (footprint "eagle-import:R0805")
      (libsource (lib "eagle-import") (part "R-EU_R0805"))
    )
    (comp (ref "R34")
      (value "8k2")
      (footprint "eagle-import:R0805")
      (libsource (lib "eagle-import") (part "R-EU_R0805"))
    )
    (comp (ref "R35")
      (value "8k2")
      (footprint "eagle-import:R0805")
      (libsource (lib "eagle-import") (part "R-EU_R0805"))
    )
    (comp (ref "R36")
      (value "100k")
      (footprint "eagle-import:R0805")
      (libsource (lib "eagle-import") (part "R-EU_R0805"))
    )
    (comp (ref "R37")
      (value "8k2")
      (footprint "eagle-import:R0805")
      (libsource (lib "eagle-import") (part "R-EU_R0805"))
    )
    (comp (ref "U$9")
      (value "IL217AT")
      (footprint "eagle-import:SOIC8")
      (libsource (lib "eagle-import") (part "IL217AT"))
    )
    (comp (ref "U$10")
      (value "IL217AT")
      (footprint "eagle-import:SOIC8")
      (libsource (lib "eagle-import") (part "IL217AT"))
    )
    (comp (ref "U$11")
      (value "IL217AT")
      (footprint "eagle-import:SOIC8")
      (libsource (lib "eagle-import") (part "IL217AT"))
    )
    (comp (ref "U$12")
      (value "IL217AT")
      (footprint "eagle-import:SOIC8")
      (libsource (lib "eagle-import") (part "IL217AT"))
    )
    (comp (ref "U$13")
      (value "IL217AT")
      (footprint "eagle-import:SOIC8")
      (libsource (lib "eagle-import") (part "IL217AT"))
    )
    (comp (ref "U$14")
      (value "IL217AT")
      (footprint "eagle-import:SOIC8")
      (libsource (lib "eagle-import") (part "IL217AT"))
    )
    (comp (ref "U$15")
      (value "IL217AT")
      (footprint "eagle-import:SOIC8")
      (libsource (lib "eagle-import") (part "IL217AT"))
    )
    (comp (ref "U$16")
      (value "IL217AT")
      (footprint "eagle-import:SOIC8")
      (libsource (lib "eagle-import") (part "IL217AT"))
    )
    (comp (ref "U$17")
      (value "IL217AT")
      (footprint "eagle-import:SOIC8")
      (libsource (lib "eagle-import") (part "IL217AT"))
    )
    (comp (ref "U$18")
      (value "IL217AT")
      (footprint "eagle-import:SOIC8")
      (libsource (lib "eagle-import") (part "IL217AT"))
    )
    (comp (ref "X16")
      (value "F09HPS")
      (footprint "eagle-import:F09HP")
      (libsource (lib "eagle-import") (part "F09HPS"))
    )
    (comp (ref "X17")
      (value "W237-02P")
      (footprint "eagle-import:W237-132")
      (libsource (lib "eagle-import") (part "W237-02P"))
    )
    (comp (ref "X18")
      (value "W237-02P")
      (footprint "eagle-import:W237-132")
      (libsource (lib "eagle-import") (part "W237-02P"))
    )
    (comp (ref "X19")
      (value "W237-02P")
      (footprint "eagle-import:W237-132")
      (libsource (lib "eagle-import") (part "W237-02P"))
    )
    (comp (ref "X20")
      (value "W237-02P")
      (footprint "eagle-import:W237-132")
      (libsource (lib "eagle-import") (part "W237-02P"))
    )
    (comp (ref "X21")
      (value "W237-02P")
      (footprint "eagle-import:W237-132")
      (libsource (lib "eagle-import") (part "W237-02P"))
    )
    (comp (ref "X22")
      (value "W237-02P")
      (footprint "eagle-import:W237-132")
      (libsource (lib "eagle-import") (part "W237-02P"))
    )
    (comp (ref "X23")
      (value "W237-02P")
      (footprint "eagle-import:W237-132")
      (libsource (lib "eagle-import") (part "W237-02P"))
    )
    (comp (ref "X24")
      (value "W237-02P")
      (footprint "eagle-import:W237-132")
      (libsource (lib "eagle-import") (part "W237-02P"))
    )
    (comp (ref "X25")
      (value "W237-02P")
      (footprint "eagle-import:W237-132")
      (libsource (lib "eagle-import") (part "W237-02P"))
    )
    (comp (ref "X26")
      (value "W237-02P")
      (footprint "eagle-import:W237-132")
      (libsource (lib "eagle-import") (part "W237-02P"))
    )
    (comp (ref "C8")
      (value "1µ")
      (footprint "eagle-import:C0805")
      (libsource (lib "eagle-import") (part "C-EUC0805"))
    )
    (comp (ref "C9")
      (value "100n")
      (footprint "eagle-import:C0805")
      (libsource (lib "eagle-import") (part "C-EUC0805"))
    )
    (comp (ref "C10")
      (value "100n")
      (footprint "eagle-import:C0805")
      (libsource (lib "eagle-import") (part "C-EUC0805"))
    )
    (comp (ref "C11")
      (value "100n")
      (footprint "eagle-import:C0805")
      (libsource (lib "eagle-import") (part "C-EUC0805"))
    )
    (comp (ref "C12")
      (value "100n")
      (footprint "eagle-import:C0805")
      (libsource (lib "eagle-import") (part "C-EUC0805"))
    )
    (comp (ref "C13")
      (value "100n")
      (footprint "eagle-import:C0805")
      (libsource (lib "eagle-import") (part "C-EUC0805"))
    )
    (comp (ref "C14")
      (value "100n")
      (footprint "eagle-import:C0805")
      (libsource (lib "eagle-import") (part "C-EUC0805"))
    )
    (comp (ref "C15")
      (value "100n")
      (footprint "eagle-import:C0805")
      (libsource (lib "eagle-import") (part "C-EUC0805"))
    )
    (comp (ref "C16")
      (value "2µ2")
      (footprint "eagle-import:C0805")
      (libsource (lib "eagle-import") (part "C-EUC0805"))
    )
    (comp (ref "C17")
      (value "1n")
      (footprint "eagle-import:C0805")
      (libsource (lib "eagle-import") (part "C-EUC0805"))
    )
    (comp (ref "C19")
      (value "10p")
      (footprint "eagle-import:C0805")
      (libsource (lib "eagle-import") (part "C-EUC0805"))
    )
    (comp (ref "C20")
      (value "10p")
      (footprint "eagle-import:C0805")
      (libsource (lib "eagle-import") (part "C-EUC0805"))
    )
    (comp (ref "LED1")
      (value "LEDSML0805")
      (footprint "eagle-import:SML0805")
      (libsource (lib "eagle-import") (part "LEDSML0805"))
    )
    (comp (ref "LED2")
      (value "LEDSML0805")
      (footprint "eagle-import:SML0805")
      (libsource (lib "eagle-import") (part "LEDSML0805"))
    )
    (comp (ref "Q1")
      (value "16M")
      (footprint "eagle-import:SM49")
      (libsource (lib "eagle-import") (part "CRYSTALSM49"))
    )
    (comp (ref "R3")
      (value "R-EU_R0805")
      (footprint "eagle-import:R0805")
      (libsource (lib "eagle-import") (part "R-EU_R0805"))
    )
    (comp (ref "R38")
      (value "R-EU_R0805")
      (footprint "eagle-import:R0805")
      (libsource (lib "eagle-import") (part "R-EU_R0805"))
    )
    (comp (ref "R39")
      (value "R-EU_R0805")
      (footprint "eagle-import:R0805")
      (libsource (lib "eagle-import") (part "R-EU_R0805"))
    )
    (comp (ref "U$2")
      (value "TM4C1233H6PM")
      (footprint "eagle-import:QFP50P1200X1200X160-64N")
      (libsource (lib "eagle-import") (part "TM4C1233H6PM"))
    )
    (comp (ref "X15")
      (value "057-006-1")
      (footprint "eagle-import:057-006-1")
      (libsource (lib "eagle-import") (part "057-006-1"))
    )
    (comp (ref "X29")
      (value "057-006-1")
      (footprint "eagle-import:057-006-1")
      (libsource (lib "eagle-import") (part "057-006-1"))
    )
  )
  (nets
    (net (code "1") (name "+3V3") (class "Default")
      (node (ref "ACTLED") (pin "A") (pinfunction "A_A") (pintype "passive"))
      (node (ref "C10") (pin "1") (pinfunction "1_1") (pintype "passive"))
      (node (ref "C11") (pin "1") (pinfunction "1_1") (pintype "passive"))
      (node (ref "C12") (pin "1") (pinfunction "1_1") (pintype "passive"))
      (node (ref "C13") (pin "1") (pinfunction "1_1") (pintype "passive"))
      (node (ref "C18") (pin "+") (pinfunction "+_+") (pintype "passive"))
      (node (ref "C21") (pin "1") (pinfunction "1_1") (pintype "passive"))
      (node (ref "C22") (pin "1") (pinfunction "1_1") (pintype "passive"))
      (node (ref "C23") (pin "1") (pinfunction "1_1") (pintype "passive"))
      (node (ref "C24") (pin "1") (pinfunction "1_1") (pintype "passive"))
      (node (ref "C38") (pin "1") (pinfunction "1_1") (pintype "passive"))
      (node (ref "C43") (pin "1") (pinfunction "1_1") (pintype "passive"))
      (node (ref "C44") (pin "1") (pinfunction "1_1") (pintype "passive"))
      (node (ref "C45") (pin "1") (pinfunction "1_1") (pintype "passive"))
      (node (ref "C46") (pin "1") (pinfunction "1_1") (pintype "passive"))
      (node (ref "C47") (pin "1") (pinfunction "1_1") (pintype "passive"))
      (node (ref "C48") (pin "1") (pinfunction "1_1") (pintype "passive"))
      (node (ref "C49") (pin "1") (pinfunction "1_1") (pintype "passive"))
      (node (ref "C50") (pin "1") (pinfunction "1_1") (pintype "passive"))
      (node (ref "C55") (pin "1") (pinfunction "1_1") (pintype "passive"))
      (node (ref "C7") (pin "2") (pinfunction "2_2") (pintype "passive"))
      (node (ref "C9") (pin "1") (pinfunction "1_1") (pintype "passive"))
      (node (ref "IC1") (pin "2") (pinfunction "OUT_2") (pintype "passive"))
      (node (ref "IC1") (pin "3") (pinfunction "OUT_3") (pintype "passive"))
      (node (ref "IC1") (pin "5") (pinfunction "SENSE_5") (pintype "input"))
      (node (ref "IC2") (pin "16") (pinfunction "VCC_16") (pintype "power_in"))
      (node (ref "LINKLED") (pin "A") (pinfunction "A_A") (pintype "passive"))
      (node (ref "R3") (pin "1") (pinfunction "1_1") (pintype "passive"))
      (node (ref "R38") (pin "1") (pinfunction "1_1") (pintype "passive"))
      (node (ref "R39") (pin "1") (pinfunction "1_1") (pintype "passive"))
      (node (ref "R40") (pin "2") (pinfunction "2_2") (pintype "passive"))
      (node (ref "R41") (pin "2") (pinfunction "2_2") (pintype "passive"))
      (node (ref "R42") (pin "2") (pinfunction "2_2") (pintype "passive"))
      (node (ref "R52") (pin "1") (pinfunction "1_1") (pintype "passive"))
      (node (ref "R53") (pin "1") (pinfunction "1_1") (pintype "passive"))
      (node (ref "R56") (pin "2") (pinfunction "2_2") (pintype "passive"))
      (node (ref "R57") (pin "2") (pinfunction "2_2") (pintype "passive"))
      (node (ref "R60") (pin "2") (pinfunction "2_2") (pintype "passive"))
      (node (ref "SPDLED") (pin "A") (pinfunction "A_A") (pintype "passive"))
      (node (ref "U$10") (pin "6") (pinfunction "COL_6") (pintype "passive"))
      (node (ref "U$11") (pin "6") (pinfunction "COL_6") (pintype "passive"))
      (node (ref "U$12") (pin "6") (pinfunction "COL_6") (pintype "passive"))
      (node (ref "U$13") (pin "6") (pinfunction "COL_6") (pintype "passive"))
      (node (ref "U$14") (pin "6") (pinfunction "COL_6") (pintype "passive"))
      (node (ref "U$15") (pin "6") (pinfunction "COL_6") (pintype "passive"))
      (node (ref "U$16") (pin "6") (pinfunction "COL_6") (pintype "passive"))
      (node (ref "U$17") (pin "6") (pinfunction "COL_6") (pintype "passive"))
      (node (ref "U$18") (pin "6") (pinfunction "COL_6") (pintype "passive"))
      (node (ref "U$19") (pin "11") (pinfunction "AVDD_11") (pintype "bidirectional"))
      (node (ref "U$19") (pin "15") (pinfunction "AVDD_15") (pintype "bidirectional"))
      (node (ref "U$19") (pin "17") (pinfunction "AVDD_17") (pintype "bidirectional"))
      (node (ref "U$19") (pin "21") (pinfunction "AVDD_21") (pintype "bidirectional"))
      (node (ref "U$19") (pin "28") (pinfunction "VDD_28") (pintype "bidirectional"))
      (node (ref "U$19") (pin "4") (pinfunction "AVDD_4") (pintype "bidirectional"))
      (node (ref "U$19") (pin "8") (pinfunction "AVDD_8") (pintype "bidirectional"))
      (node (ref "U$2") (pin "11") (pinfunction "VDD_11") (pintype "bidirectional"))
      (node (ref "U$2") (pin "2") (pinfunction "VDDA_2") (pintype "bidirectional"))
      (node (ref "U$2") (pin "26") (pinfunction "VDD_26") (pintype "bidirectional"))
      (node (ref "U$2") (pin "37") (pinfunction "VBAT_37") (pintype "bidirectional"))
      (node (ref "U$2") (pin "42") (pinfunction "VDD_42") (pintype "bidirectional"))
      (node (ref "U$2") (pin "54") (pinfunction "VDD_54") (pintype "bidirectional"))
      (node (ref "U$24") (pin "6") (pinfunction "COL_6") (pintype "passive"))
      (node (ref "U$3") (pin "24") (pinfunction "VDD_24") (pintype "bidirectional"))
      (node (ref "U$4") (pin "24") (pinfunction "VDD_24") (pintype "bidirectional"))
      (node (ref "U$5") (pin "24") (pinfunction "VDD_24") (pintype "bidirectional"))
      (node (ref "U$6") (pin "24") (pinfunction "VDD_24") (pintype "bidirectional"))
      (node (ref "U$7") (pin "24") (pinfunction "VDD_24") (pintype "bidirectional"))
      (node (ref "U$8") (pin "24") (pinfunction "VDD_24") (pintype "bidirectional"))
      (node (ref "U$9") (pin "6") (pinfunction "COL_6") (pintype "passive"))
      (node (ref "X29") (pin "1") (pinfunction "S_1") (pintype "passive"))
    )
    (net (code "2") (name "+5V") (class "Default")
      (node (ref "C5") (pin "+") (pinfunction "+_+") (pintype "passive"))
      (node (ref "C6") (pin "+") (pinfunction "+_+") (pintype "passive"))
      (node (ref "D1") (pin "A") (pinfunction "A_A") (pintype "passive"))
      (node (ref "IC1") (pin "10") (pinfunction "IN_10") (pintype "input"))
      (node (ref "IC1") (pin "11") (pinfunction "IN_11") (pintype "input"))
      (node (ref "IC1") (pin "8") (pinfunction "~{SHDN}_8") (pintype "input"))
      (node (ref "L1") (pin "P$2") (pinfunction "P$2_P$2") (pintype "bidirectional"))
      (node (ref "R1") (pin "1") (pinfunction "1_1") (pintype "passive"))
      (node (ref "U$1") (pin "4") (pinfunction "BIAS_4") (pintype "bidirectional"))
    )
    (net (code "3") (name "+24V") (class "Default")
      (node (ref "C1") (pin "1") (pinfunction "1_1") (pintype "passive"))
      (node (ref "C2") (pin "1") (pinfunction "1_1") (pintype "passive"))
      (node (ref "U$1") (pin "2") (pinfunction "VIN_2") (pintype "bidirectional"))
      (node (ref "X1") (pin "1") (pinfunction "KL_1") (pintype "passive"))
    )
    (net (code "4") (name "ACTLED") (class "Default")
      (node (ref "R51") (pin "1") (pinfunction "1_1") (pintype "passive"))
      (node (ref "U$19") (pin "27") (pinfunction "ACTLED_27") (pintype "bidirectional"))
    )
    (net (code "5") (name "AGND") (class "Default")
      (node (ref "C56") (pin "1") (pinfunction "1_1") (pintype "passive"))
      (node (ref "C57") (pin "1") (pinfunction "1_1") (pintype "passive"))
      (node (ref "C58") (pin "1") (pinfunction "1_1") (pintype "passive"))
      (node (ref "C59") (pin "1") (pinfunction "1_1") (pintype "passive"))
      (node (ref "C60") (pin "1") (pinfunction "1_1") (pintype "passive"))
      (node (ref "C61") (pin "1") (pinfunction "1_1") (pintype "passive"))
      (node (ref "C62") (pin "1") (pinfunction "1_1") (pintype "passive"))
      (node (ref "C63") (pin "1") (pinfunction "1_1") (pintype "passive"))
      (node (ref "C64") (pin "1") (pinfunction "1_1") (pintype "passive"))
      (node (ref "C65") (pin "1") (pinfunction "1_1") (pintype "passive"))
      (node (ref "U$10") (pin "2") (pinfunction "C_2") (pintype "passive"))
      (node (ref "U$11") (pin "2") (pinfunction "C_2") (pintype "passive"))
      (node (ref "U$12") (pin "2") (pinfunction "C_2") (pintype "passive"))
      (node (ref "U$13") (pin "2") (pinfunction "C_2") (pintype "passive"))
      (node (ref "U$14") (pin "2") (pinfunction "C_2") (pintype "passive"))
      (node (ref "U$15") (pin "2") (pinfunction "C_2") (pintype "passive"))
      (node (ref "U$16") (pin "2") (pinfunction "C_2") (pintype "passive"))
      (node (ref "U$17") (pin "2") (pinfunction "C_2") (pintype "passive"))
      (node (ref "U$18") (pin "2") (pinfunction "C_2") (pintype "passive"))
      (node (ref "U$9") (pin "2") (pinfunction "C_2") (pintype "passive"))
      (node (ref "X17") (pin "2") (pinfunction "KL_2") (pintype "passive"))
      (node (ref "X18") (pin "2") (pinfunction "KL_2") (pintype "passive"))
      (node (ref "X19") (pin "2") (pinfunction "KL_2") (pintype "passive"))
      (node (ref "X20") (pin "2") (pinfunction "KL_2") (pintype "passive"))
      (node (ref "X21") (pin "2") (pinfunction "KL_2") (pintype "passive"))
      (node (ref "X22") (pin "2") (pinfunction "KL_2") (pintype "passive"))
      (node (ref "X23") (pin "2") (pinfunction "KL_2") (pintype "passive"))
      (node (ref "X24") (pin "2") (pinfunction "KL_2") (pintype "passive"))
      (node (ref "X25") (pin "2") (pinfunction "KL_2") (pintype "passive"))
      (node (ref "X26") (pin "2") (pinfunction "KL_2") (pintype "passive"))
    )
    (net (code "6") (name "DIN0") (class "Default")
      (node (ref "R27") (pin "2") (pinfunction "2_2") (pintype "passive"))
      (node (ref "U$18") (pin "5") (pinfunction "EMI_5") (pintype "passive"))
      (node (ref "U$2") (pin "1") (pinfunction "PB6_1") (pintype "bidirectional"))
    )
    (net (code "7") (name "DIN1") (class "Default")
      (node (ref "R10") (pin "2") (pinfunction "2_2") (pintype "passive"))
      (node (ref "U$2") (pin "4") (pinfunction "PB7_4") (pintype "bidirectional"))
      (node (ref "U$9") (pin "5") (pinfunction "EMI_5") (pintype "passive"))
    )
    (net (code "8") (name "DIN2") (class "Default")
      (node (ref "R13") (pin "2") (pinfunction "2_2") (pintype "passive"))
      (node (ref "U$10") (pin "5") (pinfunction "EMI_5") (pintype "passive"))
      (node (ref "U$2") (pin "5") (pinfunction "PF4_5") (pintype "bidirectional"))
    )
    (net (code "9") (name "DIN3") (class "Default")
      (node (ref "R16") (pin "2") (pinfunction "2_2") (pintype "passive"))
      (node (ref "U$11") (pin "5") (pinfunction "EMI_5") (pintype "passive"))
      (node (ref "U$2") (pin "6") (pinfunction "PE3_6") (pintype "bidirectional"))
    )
    (net (code "10") (name "DIN4") (class "Default")
      (node (ref "R19") (pin "2") (pinfunction "2_2") (pintype "passive"))
      (node (ref "U$12") (pin "5") (pinfunction "EMI_5") (pintype "passive"))
      (node (ref "U$2") (pin "7") (pinfunction "PE2_7") (pintype "bidirectional"))
    )
    (net (code "11") (name "DIN5") (class "Default")
      (node (ref "R22") (pin "2") (pinfunction "2_2") (pintype "passive"))
      (node (ref "U$13") (pin "5") (pinfunction "EMI_5") (pintype "passive"))
      (node (ref "U$2") (pin "8") (pinfunction "PE1_8") (pintype "bidirectional"))
    )
    (net (code "12") (name "DIN6") (class "Default")
      (node (ref "R25") (pin "2") (pinfunction "2_2") (pintype "passive"))
      (node (ref "U$14") (pin "5") (pinfunction "EMI_5") (pintype "passive"))
      (node (ref "U$2") (pin "9") (pinfunction "PE0_9") (pintype "bidirectional"))
    )
    (net (code "13") (name "DIN7") (class "Default")
      (node (ref "R30") (pin "2") (pinfunction "2_2") (pintype "passive"))
      (node (ref "U$15") (pin "5") (pinfunction "EMI_5") (pintype "passive"))
      (node (ref "U$2") (pin "10") (pinfunction "PD7_10") (pintype "bidirectional"))
    )
    (net (code "14") (name "DIN8") (class "Default")
      (node (ref "R33") (pin "2") (pinfunction "2_2") (pintype "passive"))
      (node (ref "U$16") (pin "5") (pinfunction "EMI_5") (pintype "passive"))
      (node (ref "U$2") (pin "13") (pinfunction "PC7_13") (pintype "bidirectional"))
    )
    (net (code "15") (name "DIN9") (class "Default")
      (node (ref "R36") (pin "2") (pinfunction "2_2") (pintype "passive"))
      (node (ref "U$17") (pin "5") (pinfunction "EMI_5") (pintype "passive"))
      (node (ref "U$2") (pin "14") (pinfunction "PC6_14") (pintype "bidirectional"))
    )
    (net (code "16") (name "DISP_CLK") (class "Default")
      (node (ref "U$2") (pin "61") (pinfunction "PD0_61") (pintype "bidirectional"))
      (node (ref "X29") (pin "5") (pinfunction "S_5") (pintype "passive"))
    )
    (net (code "17") (name "DISP_CS") (class "Default")
      (node (ref "U$2") (pin "62") (pinfunction "PD1_62") (pintype "bidirectional"))
      (node (ref "X29") (pin "6") (pinfunction "S_6") (pintype "passive"))
    )
    (net (code "18") (name "DISP_SDI") (class "Default")
      (node (ref "U$2") (pin "63") (pinfunction "PD2_63") (pintype "bidirectional"))
      (node (ref "X29") (pin "4") (pinfunction "S_4") (pintype "passive"))
    )
    (net (code "19") (name "DISP_SDO") (class "Default")
      (node (ref "U$2") (pin "64") (pinfunction "PD3_64") (pintype "bidirectional"))
      (node (ref "X29") (pin "3") (pinfunction "S_3") (pintype "passive"))
    )
    (net (code "20") (name "ETH_CLK") (class "Default")
      (node (ref "U$19") (pin "33") (pinfunction "CLK_33") (pintype "bidirectional"))
      (node (ref "U$2") (pin "30") (pinfunction "PF2_30") (pintype "bidirectional"))
    )
    (net (code "21") (name "ETH_CS") (class "Default")
      (node (ref "U$19") (pin "32") (pinfunction "~{CS}_32") (pintype "bidirectional"))
      (node (ref "U$2") (pin "31") (pinfunction "PF3_31") (pintype "bidirectional"))
    )
    (net (code "22") (name "ETH_SDI") (class "Default")
      (node (ref "U$19") (pin "35") (pinfunction "SDI_35") (pintype "bidirectional"))
      (node (ref "U$2") (pin "28") (pinfunction "PF0_28") (pintype "bidirectional"))
    )
    (net (code "23") (name "ETH_SDO") (class "Default")
      (node (ref "U$19") (pin "34") (pinfunction "SDO_34") (pintype "bidirectional"))
      (node (ref "U$2") (pin "29") (pinfunction "PF1_29") (pintype "bidirectional"))
    )
    (net (code "24") (name "ETH_~{INT}") (class "Default")
      (node (ref "R53") (pin "2") (pinfunction "2_2") (pintype "passive"))
      (node (ref "U$19") (pin "36") (pinfunction "~{INT}_36") (pintype "bidirectional"))
      (node (ref "U$2") (pin "43") (pinfunction "PD4_43") (pintype "bidirectional"))
    )
    (net (code "25") (name "GND") (class "Default")
      (node (ref "C1") (pin "2") (pinfunction "2_2") (pintype "passive"))
      (node (ref "C10") (pin "2") (pinfunction "2_2") (pintype "passive"))
      (node (ref "C11") (pin "2") (pinfunction "2_2") (pintype "passive"))
      (node (ref "C12") (pin "2") (pinfunction "2_2") (pintype "passive"))
      (node (ref "C13") (pin "2") (pinfunction "2_2") (pintype "passive"))
      (node (ref "C14") (pin "2") (pinfunction "2_2") (pintype "passive"))
      (node (ref "C15") (pin "2") (pinfunction "2_2") (pintype "passive"))
      (node (ref "C16") (pin "2") (pinfunction "2_2") (pintype "passive"))
      (node (ref "C17") (pin "2") (pinfunction "2_2") (pintype "passive"))
      (node (ref "C18") (pin "-") (pinfunction "-_-") (pintype "passive"))
      (node (ref "C19") (pin "2") (pinfunction "2_2") (pintype "passive"))
      (node (ref "C2") (pin "2") (pinfunction "2_2") (pintype "passive"))
      (node (ref "C20") (pin "2") (pinfunction "2_2") (pintype "passive"))
      (node (ref "C21") (pin "2") (pinfunction "2_2") (pintype "passive"))
      (node (ref "C22") (pin "2") (pinfunction "2_2") (pintype "passive"))
      (node (ref "C23") (pin "2") (pinfunction "2_2") (pintype "passive"))
      (node (ref "C24") (pin "2") (pinfunction "2_2") (pintype "passive"))
      (node (ref "C3") (pin "2") (pinfunction "2_2") (pintype "passive"))
      (node (ref "C38") (pin "2") (pinfunction "2_2") (pintype "passive"))
      (node (ref "C41") (pin "2") (pinfunction "2_2") (pintype "passive"))
      (node (ref "C42") (pin "2") (pinfunction "2_2") (pintype "passive"))
      (node (ref "C43") (pin "2") (pinfunction "2_2") (pintype "passive"))
      (node (ref "C44") (pin "2") (pinfunction "2_2") (pintype "passive"))
      (node (ref "C45") (pin "2") (pinfunction "2_2") (pintype "passive"))
      (node (ref "C46") (pin "2") (pinfunction "2_2") (pintype "passive"))
      (node (ref "C47") (pin "2") (pinfunction "2_2") (pintype "passive"))
      (node (ref "C48") (pin "2") (pinfunction "2_2") (pintype "passive"))
      (node (ref "C49") (pin "2") (pinfunction "2_2") (pintype "passive"))
      (node (ref "C5") (pin "-") (pinfunction "-_-") (pintype "passive"))
      (node (ref "C50") (pin "2") (pinfunction "2_2") (pintype "passive"))
      (node (ref "C51") (pin "1") (pinfunction "1_1") (pintype "passive"))
      (node (ref "C52") (pin "2") (pinfunction "2_2") (pintype "passive"))
      (node (ref "C53") (pin "2") (pinfunction "2_2") (pintype "passive"))
      (node (ref "C54") (pin "2") (pinfunction "2_2") (pintype "passive"))
      (node (ref "C55") (pin "2") (pinfunction "2_2") (pintype "passive"))
      (node (ref "C6") (pin "-") (pinfunction "-_-") (pintype "passive"))
      (node (ref "C66") (pin "1") (pinfunction "1_1") (pintype "passive"))
      (node (ref "C67") (pin "1") (pinfunction "1_1") (pintype "passive"))
      (node (ref "C68") (pin "1") (pinfunction "1_1") (pintype "passive"))
      (node (ref "C69") (pin "1") (pinfunction "1_1") (pintype "passive"))
      (node (ref "C70") (pin "1") (pinfunction "1_1") (pintype "passive"))
      (node (ref "C71") (pin "1") (pinfunction "1_1") (pintype "passive"))
      (node (ref "C8") (pin "2") (pinfunction "2_2") (pintype "passive"))
      (node (ref "C9") (pin "2") (pinfunction "2_2") (pintype "passive"))
      (node (ref "D2") (pin "A") (pinfunction "A_A") (pintype "passive"))
      (node (ref "IC1") (pin "7") (pinfunction "GND_7") (pintype "power_in"))
      (node (ref "IC1") (pin "EXP") (pinfunction "EXP_EXP") (pintype "power_in"))
      (node (ref "IC2") (pin "10") (pinfunction "T2IN_10") (pintype "input"))
      (node (ref "IC2") (pin "15") (pinfunction "GND_15") (pintype "power_in"))
      (node (ref "IC2") (pin "8") (pinfunction "R2IN_8") (pintype "input"))
      (node (ref "R10") (pin "1") (pinfunction "1_1") (pintype "passive"))
      (node (ref "R13") (pin "1") (pinfunction "1_1") (pintype "passive"))
      (node (ref "R16") (pin "1") (pinfunction "1_1") (pintype "passive"))
      (node (ref "R19") (pin "1") (pinfunction "1_1") (pintype "passive"))
      (node (ref "R2") (pin "2") (pinfunction "2_2") (pintype "passive"))
      (node (ref "R22") (pin "1") (pinfunction "1_1") (pintype "passive"))
      (node (ref "R25") (pin "1") (pinfunction "1_1") (pintype "passive"))
      (node (ref "R27") (pin "1") (pinfunction "1_1") (pintype "passive"))
      (node (ref "R30") (pin "1") (pinfunction "1_1") (pintype "passive"))
      (node (ref "R33") (pin "1") (pinfunction "1_1") (pintype "passive"))
      (node (ref "R36") (pin "1") (pinfunction "1_1") (pintype "passive"))
      (node (ref "R43") (pin "2") (pinfunction "2_2") (pintype "passive"))
      (node (ref "R44") (pin "2") (pinfunction "2_2") (pintype "passive"))
      (node (ref "R45") (pin "2") (pinfunction "2_2") (pintype "passive"))
      (node (ref "R46") (pin "2") (pinfunction "2_2") (pintype "passive"))
      (node (ref "R47") (pin "2") (pinfunction "2_2") (pintype "passive"))
      (node (ref "R48") (pin "2") (pinfunction "2_2") (pintype "passive"))
      (node (ref "R5") (pin "1") (pinfunction "1_1") (pintype "passive"))
      (node (ref "R54") (pin "1") (pinfunction "1_1") (pintype "passive"))
      (node (ref "U$1") (pin "6") (pinfunction "GND_6") (pintype "bidirectional"))
      (node (ref "U$19") (pin "14") (pinfunction "AGND_14") (pintype "bidirectional"))
      (node (ref "U$19") (pin "16") (pinfunction "AGND_16") (pintype "bidirectional"))
      (node (ref "U$19") (pin "19") (pinfunction "AGND_19") (pintype "bidirectional"))
      (node (ref "U$19") (pin "29") (pinfunction "GND_29") (pintype "bidirectional"))
      (node (ref "U$19") (pin "3") (pinfunction "AGND_3") (pintype "bidirectional"))
      (node (ref "U$19") (pin "48") (pinfunction "AGND_48") (pintype "bidirectional"))
      (node (ref "U$19") (pin "9") (pinfunction "AGND_9") (pintype "bidirectional"))
      (node (ref "U$2") (pin "12") (pinfunction "GND_12") (pintype "bidirectional"))
      (node (ref "U$2") (pin "27") (pinfunction "GND_27") (pintype "bidirectional"))
      (node (ref "U$2") (pin "3") (pinfunction "GNDA_3") (pintype "bidirectional"))
      (node (ref "U$2") (pin "32") (pinfunction "~{WAKE}_32") (pintype "bidirectional"))
      (node (ref "U$2") (pin "34") (pinfunction "XOSC0_34") (pintype "bidirectional"))
      (node (ref "U$2") (pin "35") (pinfunction "GNDX_35") (pintype "bidirectional"))
      (node (ref "U$2") (pin "39") (pinfunction "GND_39") (pintype "bidirectional"))
      (node (ref "U$2") (pin "55") (pinfunction "GND_55") (pintype "bidirectional"))
      (node (ref "U$3") (pin "1") (pinfunction "PGNDA_1") (pintype "bidirectional"))
      (node (ref "U$3") (pin "12") (pinfunction "AGND_12") (pintype "bidirectional"))
      (node (ref "U$3") (pin "19") (pinfunction "PGNDB_19") (pintype "bidirectional"))
      (node (ref "U$3") (pin "28") (pinfunction "DGND_28") (pintype "bidirectional"))
      (node (ref "U$3") (pin "37") (pinfunction "EPAD_37") (pintype "bidirectional"))
      (node (ref "U$4") (pin "1") (pinfunction "PGNDA_1") (pintype "bidirectional"))
      (node (ref "U$4") (pin "12") (pinfunction "AGND_12") (pintype "bidirectional"))
      (node (ref "U$4") (pin "19") (pinfunction "PGNDB_19") (pintype "bidirectional"))
      (node (ref "U$4") (pin "28") (pinfunction "DGND_28") (pintype "bidirectional"))
      (node (ref "U$4") (pin "37") (pinfunction "EPAD_37") (pintype "bidirectional"))
      (node (ref "U$5") (pin "1") (pinfunction "PGNDA_1") (pintype "bidirectional"))
      (node (ref "U$5") (pin "12") (pinfunction "AGND_12") (pintype "bidirectional"))
      (node (ref "U$5") (pin "19") (pinfunction "PGNDB_19") (pintype "bidirectional"))
      (node (ref "U$5") (pin "28") (pinfunction "DGND_28") (pintype "bidirectional"))
      (node (ref "U$5") (pin "37") (pinfunction "EPAD_37") (pintype "bidirectional"))
      (node (ref "U$6") (pin "1") (pinfunction "PGNDA_1") (pintype "bidirectional"))
      (node (ref "U$6") (pin "12") (pinfunction "AGND_12") (pintype "bidirectional"))
      (node (ref "U$6") (pin "19") (pinfunction "PGNDB_19") (pintype "bidirectional"))
      (node (ref "U$6") (pin "28") (pinfunction "DGND_28") (pintype "bidirectional"))
      (node (ref "U$6") (pin "37") (pinfunction "EPAD_37") (pintype "bidirectional"))
      (node (ref "U$7") (pin "1") (pinfunction "PGNDA_1") (pintype "bidirectional"))
      (node (ref "U$7") (pin "12") (pinfunction "AGND_12") (pintype "bidirectional"))
      (node (ref "U$7") (pin "19") (pinfunction "PGNDB_19") (pintype "bidirectional"))
      (node (ref "U$7") (pin "28") (pinfunction "DGND_28") (pintype "bidirectional"))
      (node (ref "U$7") (pin "37") (pinfunction "EPAD_37") (pintype "bidirectional"))
      (node (ref "U$8") (pin "1") (pinfunction "PGNDA_1") (pintype "bidirectional"))
      (node (ref "U$8") (pin "12") (pinfunction "AGND_12") (pintype "bidirectional"))
      (node (ref "U$8") (pin "19") (pinfunction "PGNDB_19") (pintype "bidirectional"))
      (node (ref "U$8") (pin "28") (pinfunction "DGND_28") (pintype "bidirectional"))
      (node (ref "U$8") (pin "37") (pinfunction "EPAD_37") (pintype "bidirectional"))
      (node (ref "X1") (pin "2") (pinfunction "KL_2") (pintype "passive"))
      (node (ref "X15") (pin "6") (pinfunction "S_6") (pintype "passive"))
      (node (ref "X16") (pin "G1") (pinfunction "G1_G1") (pintype "passive"))
      (node (ref "X28") (pin "1") (pinfunction "KL_1") (pintype "passive"))
      (node (ref "X29") (pin "2") (pinfunction "S_2") (pintype "passive"))
    )
    (net (code "26") (name "GNDINT") (class "Default")
      (node (ref "C72") (pin "1") (pinfunction "1_1") (pintype "passive"))
      (node (ref "U$24") (pin "2") (pinfunction "C_2") (pintype "passive"))
      (node (ref "X2") (pin "2") (pinfunction "KL_2") (pintype "passive"))
    )
    (net (code "27") (name "HARDSTOP") (class "Default")
      (node (ref "R5") (pin "2") (pinfunction "2_2") (pintype "passive"))
      (node (ref "U$24") (pin "5") (pinfunction "EMI_5") (pintype "passive"))
      (node (ref "U$3") (pin "7") (pinfunction "SW_7") (pintype "bidirectional"))
      (node (ref "U$4") (pin "7") (pinfunction "SW_7") (pintype "bidirectional"))
      (node (ref "U$5") (pin "7") (pinfunction "SW_7") (pintype "bidirectional"))
      (node (ref "U$6") (pin "7") (pinfunction "SW_7") (pintype "bidirectional"))
      (node (ref "U$7") (pin "7") (pinfunction "SW_7") (pintype "bidirectional"))
      (node (ref "U$8") (pin "7") (pinfunction "SW_7") (pintype "bidirectional"))
    )
    (net (code "28") (name "JTAG_TCK") (class "Default")
      (node (ref "U$2") (pin "52") (pinfunction "PC0/TCK/DWCLK_52") (pintype "bidirectional"))
      (node (ref "X15") (pin "1") (pinfunction "S_1") (pintype "passive"))
    )
    (net (code "29") (name "JTAG_TDI") (class "Default")
      (node (ref "U$2") (pin "50") (pinfunction "PC2/TDI_50") (pintype "bidirectional"))
      (node (ref "X15") (pin "3") (pinfunction "S_3") (pintype "passive"))
    )
    (net (code "30") (name "JTAG_TDO") (class "Default")
      (node (ref "U$2") (pin "49") (pinfunction "PC3/TDO/SWO_49") (pintype "bidirectional"))
      (node (ref "X15") (pin "4") (pinfunction "S_4") (pintype "passive"))
    )
    (net (code "31") (name "JTAG_TMS") (class "Default")
      (node (ref "U$2") (pin "51") (pinfunction "PC1/TMS/SWDIO_51") (pintype "bidirectional"))
      (node (ref "X15") (pin "2") (pinfunction "S_2") (pintype "passive"))
    )
    (net (code "32") (name "JTAG_~{RST}") (class "Default")
      (node (ref "C17") (pin "1") (pinfunction "1_1") (pintype "passive"))
      (node (ref "R3") (pin "2") (pinfunction "2_2") (pintype "passive"))
      (node (ref "U$2") (pin "38") (pinfunction "~{RST}_38") (pintype "bidirectional"))
      (node (ref "X15") (pin "5") (pinfunction "S_5") (pintype "passive"))
    )
    (net (code "33") (name "LINKLED") (class "Default")
      (node (ref "R50") (pin "1") (pinfunction "1_1") (pintype "passive"))
      (node (ref "U$19") (pin "25") (pinfunction "LINKLED_25") (pintype "bidirectional"))
    )
    (net (code "34") (name "Net-(ACTLED-PadC)") (class "Default")
      (node (ref "ACTLED") (pin "C") (pinfunction "C_C") (pintype "passive"))
      (node (ref "R51") (pin "2") (pinfunction "2_2") (pintype "passive"))
    )
    (net (code "35") (name "Net-(D3-AC)") (class "Default")
      (node (ref "C26") (pin "2") (pinfunction "2_2") (pintype "passive"))
      (node (ref "D3") (pin "3") (pinfunction "AC_3") (pintype "passive"))
    )
    (net (code "36") (name "Net-(D3-C)") (class "Default")
      (node (ref "C27") (pin "2") (pinfunction "2_2") (pintype "passive"))
      (node (ref "D3") (pin "2") (pinfunction "C_2") (pintype "passive"))
      (node (ref "U$3") (pin "14") (pinfunction "VBOOT_14") (pintype "bidirectional"))
    )
    (net (code "37") (name "Net-(D4-AC)") (class "Default")
      (node (ref "C28") (pin "2") (pinfunction "2_2") (pintype "passive"))
      (node (ref "D4") (pin "3") (pinfunction "AC_3") (pintype "passive"))
    )
    (net (code "38") (name "Net-(D4-C)") (class "Default")
      (node (ref "C29") (pin "2") (pinfunction "2_2") (pintype "passive"))
      (node (ref "D4") (pin "2") (pinfunction "C_2") (pintype "passive"))
      (node (ref "U$4") (pin "14") (pinfunction "VBOOT_14") (pintype "bidirectional"))
    )
    (net (code "39") (name "Net-(D5-AC)") (class "Default")
      (node (ref "C30") (pin "2") (pinfunction "2_2") (pintype "passive"))
      (node (ref "D5") (pin "3") (pinfunction "AC_3") (pintype "passive"))
    )
    (net (code "40") (name "Net-(D5-C)") (class "Default")
      (node (ref "C31") (pin "2") (pinfunction "2_2") (pintype "passive"))
      (node (ref "D5") (pin "2") (pinfunction "C_2") (pintype "passive"))
      (node (ref "U$5") (pin "14") (pinfunction "VBOOT_14") (pintype "bidirectional"))
    )
    (net (code "41") (name "Net-(D6-AC)") (class "Default")
      (node (ref "C32") (pin "2") (pinfunction "2_2") (pintype "passive"))
      (node (ref "D6") (pin "3") (pinfunction "AC_3") (pintype "passive"))
    )
    (net (code "42") (name "Net-(D6-C)") (class "Default")
      (node (ref "C33") (pin "2") (pinfunction "2_2") (pintype "passive"))
      (node (ref "D6") (pin "2") (pinfunction "C_2") (pintype "passive"))
      (node (ref "U$6") (pin "14") (pinfunction "VBOOT_14") (pintype "bidirectional"))
    )
    (net (code "43") (name "Net-(D7-AC)") (class "Default")
      (node (ref "C34") (pin "2") (pinfunction "2_2") (pintype "passive"))
      (node (ref "D7") (pin "3") (pinfunction "AC_3") (pintype "passive"))
    )
    (net (code "44") (name "Net-(D7-C)") (class "Default")
      (node (ref "C35") (pin "2") (pinfunction "2_2") (pintype "passive"))
      (node (ref "D7") (pin "2") (pinfunction "C_2") (pintype "passive"))
      (node (ref "U$7") (pin "14") (pinfunction "VBOOT_14") (pintype "bidirectional"))
    )
    (net (code "45") (name "Net-(D8-AC)") (class "Default")
      (node (ref "C36") (pin "2") (pinfunction "2_2") (pintype "passive"))
      (node (ref "D8") (pin "3") (pinfunction "AC_3") (pintype "passive"))
    )
    (net (code "46") (name "Net-(D8-C)") (class "Default")
      (node (ref "C37") (pin "2") (pinfunction "2_2") (pintype "passive"))
      (node (ref "D8") (pin "2") (pinfunction "C_2") (pintype "passive"))
      (node (ref "U$8") (pin "14") (pinfunction "VBOOT_14") (pintype "bidirectional"))
    )
    (net (code "47") (name "Net-(IC1-BYP)") (class "Default")
      (node (ref "C7") (pin "1") (pinfunction "1_1") (pintype "passive"))
      (node (ref "IC1") (pin "6") (pinfunction "BYP_6") (pintype "input"))
    )
    (net (code "48") (name "Net-(IC2A-C1+)") (class "Default")
      (node (ref "C39") (pin "1") (pinfunction "1_1") (pintype "passive"))
      (node (ref "IC2") (pin "1") (pinfunction "C1+_1") (pintype "bidirectional"))
    )
    (net (code "49") (name "Net-(IC2A-C1-)") (class "Default")
      (node (ref "C39") (pin "2") (pinfunction "2_2") (pintype "passive"))
      (node (ref "IC2") (pin "3") (pinfunction "C1-_3") (pintype "bidirectional"))
    )
    (net (code "50") (name "Net-(IC2A-C2+)") (class "Default")
      (node (ref "C40") (pin "1") (pinfunction "1_1") (pintype "passive"))
      (node (ref "IC2") (pin "4") (pinfunction "C2+_4") (pintype "bidirectional"))
    )
    (net (code "51") (name "Net-(IC2A-C2-)") (class "Default")
      (node (ref "C40") (pin "2") (pinfunction "2_2") (pintype "passive"))
      (node (ref "IC2") (pin "5") (pinfunction "C2-_5") (pintype "bidirectional"))
    )
    (net (code "52") (name "Net-(IC2A-V+)") (class "Default")
      (node (ref "C41") (pin "1") (pinfunction "1_1") (pintype "passive"))
      (node (ref "IC2") (pin "2") (pinfunction "V+_2") (pintype "bidirectional"))
    )
    (net (code "53") (name "Net-(IC2A-V-)") (class "Default")
      (node (ref "C42") (pin "1") (pinfunction "1_1") (pintype "passive"))
      (node (ref "IC2") (pin "6") (pinfunction "V-_6") (pintype "bidirectional"))
    )
    (net (code "54") (name "Net-(LED1-PadA)") (class "Default")
      (node (ref "LED1") (pin "A") (pinfunction "A_A") (pintype "passive"))
      (node (ref "R38") (pin "2") (pinfunction "2_2") (pintype "passive"))
    )
    (net (code "55") (name "Net-(LED2-PadA)") (class "Default")
      (node (ref "LED2") (pin "A") (pinfunction "A_A") (pintype "passive"))
      (node (ref "R39") (pin "2") (pinfunction "2_2") (pintype "passive"))
    )
    (net (code "56") (name "Net-(LINKLED-PadC)") (class "Default")
      (node (ref "LINKLED") (pin "C") (pinfunction "C_C") (pintype "passive"))
      (node (ref "R50") (pin "2") (pinfunction "2_2") (pintype "passive"))
    )
    (net (code "57") (name "Net-(R43-Pad1)") (class "Default")
      (node (ref "R43") (pin "1") (pinfunction "1_1") (pintype "passive"))
      (node (ref "U$19") (pin "23") (pinfunction "RSVD_23") (pintype "bidirectional"))
    )
    (net (code "58") (name "Net-(R44-Pad1)") (class "Default")
      (node (ref "R44") (pin "1") (pinfunction "1_1") (pintype "passive"))
      (node (ref "U$19") (pin "38") (pinfunction "RSVD_38") (pintype "bidirectional"))
    )
    (net (code "59") (name "Net-(R45-Pad1)") (class "Default")
      (node (ref "R45") (pin "1") (pinfunction "1_1") (pintype "passive"))
      (node (ref "U$19") (pin "39") (pinfunction "RSVD_39") (pintype "bidirectional"))
    )
    (net (code "60") (name "Net-(R46-Pad1)") (class "Default")
      (node (ref "R46") (pin "1") (pinfunction "1_1") (pintype "passive"))
      (node (ref "U$19") (pin "40") (pinfunction "RSVD_40") (pintype "bidirectional"))
    )
    (net (code "61") (name "Net-(R47-Pad1)") (class "Default")
      (node (ref "R47") (pin "1") (pinfunction "1_1") (pintype "passive"))
      (node (ref "U$19") (pin "41") (pinfunction "RSVD_41") (pintype "bidirectional"))
    )
    (net (code "62") (name "Net-(R48-Pad1)") (class "Default")
      (node (ref "R48") (pin "1") (pinfunction "1_1") (pintype "passive"))
      (node (ref "U$19") (pin "42") (pinfunction "RSVD_42") (pintype "bidirectional"))
    )
    (net (code "63") (name "Net-(R49-Pad2)") (class "Default")
      (node (ref "R49") (pin "2") (pinfunction "2_2") (pintype "passive"))
      (node (ref "SPDLED") (pin "C") (pinfunction "C_C") (pintype "passive"))
    )
    (net (code "64") (name "Net-(U$1-BOOST)") (class "Default")
      (node (ref "C4") (pin "1") (pinfunction "1_1") (pintype "passive"))
      (node (ref "D1") (pin "C") (pinfunction "C_C") (pintype "passive"))
      (node (ref "U$1") (pin "1") (pinfunction "BOOST_1") (pintype "bidirectional"))
    )
    (net (code "65") (name "Net-(U$1-FB)") (class "Default")
      (node (ref "R1") (pin "2") (pinfunction "2_2") (pintype "passive"))
      (node (ref "R2") (pin "1") (pinfunction "1_1") (pintype "passive"))
      (node (ref "U$1") (pin "7") (pinfunction "FB_7") (pintype "bidirectional"))
    )
    (net (code "66") (name "Net-(U$1-VC)") (class "Default")
      (node (ref "C3") (pin "1") (pinfunction "1_1") (pintype "passive"))
      (node (ref "U$1") (pin "8") (pinfunction "VC_8") (pintype "bidirectional"))
    )
    (net (code "67") (name "Net-(U$1-VSW)") (class "Default")
      (node (ref "C4") (pin "2") (pinfunction "2_2") (pintype "passive"))
      (node (ref "D2") (pin "C") (pinfunction "C_C") (pintype "passive"))
      (node (ref "L1") (pin "P$1") (pinfunction "P$1_P$1") (pintype "bidirectional"))
      (node (ref "U$1") (pin "3") (pinfunction "VSW_3") (pintype "bidirectional"))
    )
    (net (code "68") (name "Net-(U$2A-OSC0)") (class "Default")
      (node (ref "C20") (pin "1") (pinfunction "1_1") (pintype "passive"))
      (node (ref "Q1") (pin "1") (pinfunction "1_1") (pintype "passive"))
      (node (ref "U$2") (pin "40") (pinfunction "OSC0_40") (pintype "bidirectional"))
    )
    (net (code "69") (name "Net-(U$2A-OSC1)") (class "Default")
      (node (ref "C19") (pin "1") (pinfunction "1_1") (pintype "passive"))
      (node (ref "Q1") (pin "2") (pinfunction "2_2") (pintype "passive"))
      (node (ref "U$2") (pin "41") (pinfunction "OSC1_41") (pintype "bidirectional"))
    )
    (net (code "70") (name "Net-(U$2A-PB2{slash}IC20SCL)") (class "Default")
      (node (ref "LED2") (pin "C") (pinfunction "C_C") (pintype "passive"))
      (node (ref "U$2") (pin "47") (pinfunction "PB2/IC20SCL_47") (pintype "bidirectional"))
    )
    (net (code "71") (name "Net-(U$2A-PB3{slash}IC2C0SDA)") (class "Default")
      (node (ref "LED1") (pin "C") (pinfunction "C_C") (pintype "passive"))
      (node (ref "U$2") (pin "48") (pinfunction "PB3/IC2C0SDA_48") (pintype "bidirectional"))
    )
    (net (code "72") (name "Net-(U$3-CP)") (class "Default")
      (node (ref "C26") (pin "1") (pinfunction "1_1") (pintype "passive"))
      (node (ref "U$3") (pin "13") (pinfunction "CP_13") (pintype "bidirectional"))
    )
    (net (code "73") (name "Net-(U$3-SDO)") (class "Default")
      (node (ref "U$3") (pin "25") (pinfunction "SDO_25") (pintype "bidirectional"))
      (node (ref "U$4") (pin "27") (pinfunction "SDI_27") (pintype "bidirectional"))
    )
    (net (code "74") (name "Net-(U$3-VREG)") (class "Default")
      (node (ref "C66") (pin "2") (pinfunction "2_2") (pintype "passive"))
      (node (ref "U$3") (pin "9") (pinfunction "VREG_9") (pintype "bidirectional"))
    )
    (net (code "75") (name "Net-(U$4-CP)") (class "Default")
      (node (ref "C28") (pin "1") (pinfunction "1_1") (pintype "passive"))
      (node (ref "U$4") (pin "13") (pinfunction "CP_13") (pintype "bidirectional"))
    )
    (net (code "76") (name "Net-(U$4-SDO)") (class "Default")
      (node (ref "U$4") (pin "25") (pinfunction "SDO_25") (pintype "bidirectional"))
      (node (ref "U$5") (pin "27") (pinfunction "SDI_27") (pintype "bidirectional"))
    )
    (net (code "77") (name "Net-(U$4-VREG)") (class "Default")
      (node (ref "C67") (pin "2") (pinfunction "2_2") (pintype "passive"))
      (node (ref "U$4") (pin "9") (pinfunction "VREG_9") (pintype "bidirectional"))
    )
    (net (code "78") (name "Net-(U$5-CP)") (class "Default")
      (node (ref "C30") (pin "1") (pinfunction "1_1") (pintype "passive"))
      (node (ref "U$5") (pin "13") (pinfunction "CP_13") (pintype "bidirectional"))
    )
    (net (code "79") (name "Net-(U$5-VREG)") (class "Default")
      (node (ref "C68") (pin "2") (pinfunction "2_2") (pintype "passive"))
      (node (ref "U$5") (pin "9") (pinfunction "VREG_9") (pintype "bidirectional"))
    )
    (net (code "80") (name "Net-(U$6-CP)") (class "Default")
      (node (ref "C32") (pin "1") (pinfunction "1_1") (pintype "passive"))
      (node (ref "U$6") (pin "13") (pinfunction "CP_13") (pintype "bidirectional"))
    )
    (net (code "81") (name "Net-(U$6-SDO)") (class "Default")
      (node (ref "U$6") (pin "25") (pinfunction "SDO_25") (pintype "bidirectional"))
      (node (ref "U$7") (pin "27") (pinfunction "SDI_27") (pintype "bidirectional"))
    )
    (net (code "82") (name "Net-(U$6-VREG)") (class "Default")
      (node (ref "C71") (pin "2") (pinfunction "2_2") (pintype "passive"))
      (node (ref "U$6") (pin "9") (pinfunction "VREG_9") (pintype "bidirectional"))
    )
    (net (code "83") (name "Net-(U$7-CP)") (class "Default")
      (node (ref "C34") (pin "1") (pinfunction "1_1") (pintype "passive"))
      (node (ref "U$7") (pin "13") (pinfunction "CP_13") (pintype "bidirectional"))
    )
    (net (code "84") (name "Net-(U$7-SDO)") (class "Default")
      (node (ref "U$7") (pin "25") (pinfunction "SDO_25") (pintype "bidirectional"))
      (node (ref "U$8") (pin "27") (pinfunction "SDI_27") (pintype "bidirectional"))
    )
    (net (code "85") (name "Net-(U$7-VREG)") (class "Default")
      (node (ref "C70") (pin "2") (pinfunction "2_2") (pintype "passive"))
      (node (ref "U$7") (pin "9") (pinfunction "VREG_9") (pintype "bidirectional"))
    )
    (net (code "86") (name "Net-(U$8-CP)") (class "Default")
      (node (ref "C36") (pin "1") (pinfunction "1_1") (pintype "passive"))
      (node (ref "U$8") (pin "13") (pinfunction "CP_13") (pintype "bidirectional"))
    )
    (net (code "87") (name "Net-(U$8-VREG)") (class "Default")
      (node (ref "C69") (pin "2") (pinfunction "2_2") (pintype "passive"))
      (node (ref "U$8") (pin "9") (pinfunction "VREG_9") (pintype "bidirectional"))
    )
    (net (code "88") (name "Net-(U$9-A)") (class "Default")
      (node (ref "C61") (pin "2") (pinfunction "2_2") (pintype "passive"))
      (node (ref "R11") (pin "2") (pinfunction "2_2") (pintype "passive"))
      (node (ref "R9") (pin "2") (pinfunction "2_2") (pintype "passive"))
      (node (ref "U$9") (pin "1") (pinfunction "A_1") (pintype "passive"))
    )
    (net (code "89") (name "Net-(U$10-A)") (class "Default")
      (node (ref "C62") (pin "2") (pinfunction "2_2") (pintype "passive"))
      (node (ref "R12") (pin "2") (pinfunction "2_2") (pintype "passive"))
      (node (ref "R14") (pin "2") (pinfunction "2_2") (pintype "passive"))
      (node (ref "U$10") (pin "1") (pinfunction "A_1") (pintype "passive"))
    )
    (net (code "90") (name "Net-(U$11-A)") (class "Default")
      (node (ref "C57") (pin "2") (pinfunction "2_2") (pintype "passive"))
      (node (ref "R15") (pin "2") (pinfunction "2_2") (pintype "passive"))
      (node (ref "R17") (pin "2") (pinfunction "2_2") (pintype "passive"))
      (node (ref "U$11") (pin "1") (pinfunction "A_1") (pintype "passive"))
    )
    (net (code "91") (name "Net-(U$12-A)") (class "Default")
      (node (ref "C60") (pin "2") (pinfunction "2_2") (pintype "passive"))
      (node (ref "R18") (pin "2") (pinfunction "2_2") (pintype "passive"))
      (node (ref "R20") (pin "2") (pinfunction "2_2") (pintype "passive"))
      (node (ref "U$12") (pin "1") (pinfunction "A_1") (pintype "passive"))
    )
    (net (code "92") (name "Net-(U$13-A)") (class "Default")
      (node (ref "C63") (pin "2") (pinfunction "2_2") (pintype "passive"))
      (node (ref "R21") (pin "2") (pinfunction "2_2") (pintype "passive"))
      (node (ref "R23") (pin "2") (pinfunction "2_2") (pintype "passive"))
      (node (ref "U$13") (pin "1") (pinfunction "A_1") (pintype "passive"))
    )
    (net (code "93") (name "Net-(U$14-A)") (class "Default")
      (node (ref "C58") (pin "2") (pinfunction "2_2") (pintype "passive"))
      (node (ref "R24") (pin "2") (pinfunction "2_2") (pintype "passive"))
      (node (ref "R28") (pin "2") (pinfunction "2_2") (pintype "passive"))
      (node (ref "U$14") (pin "1") (pinfunction "A_1") (pintype "passive"))
    )
    (net (code "94") (name "Net-(U$15-A)") (class "Default")
      (node (ref "C59") (pin "2") (pinfunction "2_2") (pintype "passive"))
      (node (ref "R29") (pin "2") (pinfunction "2_2") (pintype "passive"))
      (node (ref "R31") (pin "2") (pinfunction "2_2") (pintype "passive"))
      (node (ref "U$15") (pin "1") (pinfunction "A_1") (pintype "passive"))
    )
    (net (code "95") (name "Net-(U$16-A)") (class "Default")
      (node (ref "C64") (pin "2") (pinfunction "2_2") (pintype "passive"))
      (node (ref "R32") (pin "2") (pinfunction "2_2") (pintype "passive"))
      (node (ref "R34") (pin "2") (pinfunction "2_2") (pintype "passive"))
      (node (ref "U$16") (pin "1") (pinfunction "A_1") (pintype "passive"))
    )
    (net (code "96") (name "Net-(U$17-A)") (class "Default")
      (node (ref "C65") (pin "2") (pinfunction "2_2") (pintype "passive"))
      (node (ref "R35") (pin "2") (pinfunction "2_2") (pintype "passive"))
      (node (ref "R37") (pin "2") (pinfunction "2_2") (pintype "passive"))
      (node (ref "U$17") (pin "1") (pinfunction "A_1") (pintype "passive"))
    )
    (net (code "97") (name "Net-(U$18-A)") (class "Default")
      (node (ref "C56") (pin "2") (pinfunction "2_2") (pintype "passive"))
      (node (ref "R26") (pin "2") (pinfunction "2_2") (pintype "passive"))
      (node (ref "R6") (pin "2") (pinfunction "2_2") (pintype "passive"))
      (node (ref "U$18") (pin "1") (pinfunction "A_1") (pintype "passive"))
    )
    (net (code "98") (name "Net-(U$19A-EXRES1)") (class "Default")
      (node (ref "R54") (pin "2") (pinfunction "2_2") (pintype "passive"))
      (node (ref "U$19") (pin "10") (pinfunction "EXRES1_10") (pintype "bidirectional"))
    )
    (net (code "99") (name "Net-(U$19A-PMODE0)") (class "Default")
      (node (ref "R42") (pin "1") (pinfunction "1_1") (pintype "passive"))
      (node (ref "U$19") (pin "45") (pinfunction "PMODE0_45") (pintype "bidirectional"))
    )
    (net (code "100") (name "Net-(U$19A-PMODE1)") (class "Default")
      (node (ref "R41") (pin "1") (pinfunction "1_1") (pintype "passive"))
      (node (ref "U$19") (pin "44") (pinfunction "PMODE1_44") (pintype "bidirectional"))
    )
    (net (code "101") (name "Net-(U$19A-PMODE2)") (class "Default")
      (node (ref "R40") (pin "1") (pinfunction "1_1") (pintype "passive"))
      (node (ref "U$19") (pin "43") (pinfunction "PMODE2_43") (pintype "bidirectional"))
    )
    (net (code "102") (name "Net-(U$19A-TOCAP)") (class "Default")
      (node (ref "C51") (pin "2") (pinfunction "2_2") (pintype "passive"))
      (node (ref "U$19") (pin "20") (pinfunction "TOCAP_20") (pintype "bidirectional"))
    )
    (net (code "103") (name "Net-(U$19A-XI{slash}CLKIN)") (class "Default")
      (node (ref "C53") (pin "1") (pinfunction "1_1") (pintype "passive"))
      (node (ref "Q2") (pin "2") (pinfunction "2_2") (pintype "passive"))
      (node (ref "R55") (pin "2") (pinfunction "2_2") (pintype "passive"))
      (node (ref "U$19") (pin "30") (pinfunction "XI/CLKIN_30") (pintype "bidirectional"))
    )
    (net (code "104") (name "Net-(U$19A-XO)") (class "Default")
      (node (ref "C52") (pin "1") (pinfunction "1_1") (pintype "passive"))
      (node (ref "Q2") (pin "1") (pinfunction "1_1") (pintype "passive"))
      (node (ref "R55") (pin "1") (pinfunction "1_1") (pintype "passive"))
      (node (ref "U$19") (pin "31") (pinfunction "XO_31") (pintype "bidirectional"))
    )
    (net (code "105") (name "Net-(U$19A-~{RST})") (class "Default")
      (node (ref "R52") (pin "2") (pinfunction "2_2") (pintype "passive"))
      (node (ref "U$19") (pin "37") (pinfunction "~{RST}_37") (pintype "bidirectional"))
    )
    (net (code "106") (name "Net-(U$24-A)") (class "Default")
      (node (ref "C72") (pin "2") (pinfunction "2_2") (pintype "passive"))
      (node (ref "R4") (pin "2") (pinfunction "2_2") (pintype "passive"))
      (node (ref "R7") (pin "2") (pinfunction "2_2") (pintype "passive"))
      (node (ref "U$24") (pin "1") (pinfunction "A_1") (pintype "passive"))
    )
    (net (code "107") (name "Net-(X2A-KL)") (class "Default")
      (node (ref "R4") (pin "1") (pinfunction "1_1") (pintype "passive"))
      (node (ref "R7") (pin "1") (pinfunction "1_1") (pintype "passive"))
      (node (ref "X2") (pin "1") (pinfunction "KL_1") (pintype "passive"))
    )
    (net (code "108") (name "Net-(X3A-KL)") (class "Default")
      (node (ref "U$3") (pin "2") (pinfunction "OUT1A_2") (pintype "bidirectional"))
      (node (ref "U$3") (pin "3") (pinfunction "OUT1A_3") (pintype "bidirectional"))
      (node (ref "X3") (pin "1") (pinfunction "KL_1") (pintype "passive"))
    )
    (net (code "109") (name "Net-(X3B-KL)") (class "Default")
      (node (ref "U$3") (pin "35") (pinfunction "OUT2A_35") (pintype "bidirectional"))
      (node (ref "U$3") (pin "36") (pinfunction "OUT2A_36") (pintype "bidirectional"))
      (node (ref "X3") (pin "2") (pinfunction "KL_2") (pintype "passive"))
    )
    (net (code "110") (name "Net-(X4A-KL)") (class "Default")
      (node (ref "U$3") (pin "17") (pinfunction "OUT1B_17") (pintype "bidirectional"))
      (node (ref "U$3") (pin "18") (pinfunction "OUT1B_18") (pintype "bidirectional"))
      (node (ref "X4") (pin "1") (pinfunction "KL_1") (pintype "passive"))
    )
    (net (code "111") (name "Net-(X4B-KL)") (class "Default")
      (node (ref "U$3") (pin "20") (pinfunction "OUT2B_20") (pintype "bidirectional"))
      (node (ref "U$3") (pin "21") (pinfunction "OUT2B_21") (pintype "bidirectional"))
      (node (ref "X4") (pin "2") (pinfunction "KL_2") (pintype "passive"))
    )
    (net (code "112") (name "Net-(X5A-KL)") (class "Default")
      (node (ref "U$4") (pin "2") (pinfunction "OUT1A_2") (pintype "bidirectional"))
      (node (ref "U$4") (pin "3") (pinfunction "OUT1A_3") (pintype "bidirectional"))
      (node (ref "X5") (pin "1") (pinfunction "KL_1") (pintype "passive"))
    )
    (net (code "113") (name "Net-(X5B-KL)") (class "Default")
      (node (ref "U$4") (pin "35") (pinfunction "OUT2A_35") (pintype "bidirectional"))
      (node (ref "U$4") (pin "36") (pinfunction "OUT2A_36") (pintype "bidirectional"))
      (node (ref "X5") (pin "2") (pinfunction "KL_2") (pintype "passive"))
    )
    (net (code "114") (name "Net-(X6A-KL)") (class "Default")
      (node (ref "U$4") (pin "17") (pinfunction "OUT1B_17") (pintype "bidirectional"))
      (node (ref "U$4") (pin "18") (pinfunction "OUT1B_18") (pintype "bidirectional"))
      (node (ref "X6") (pin "1") (pinfunction "KL_1") (pintype "passive"))
    )
    (net (code "115") (name "Net-(X6B-KL)") (class "Default")
      (node (ref "U$4") (pin "20") (pinfunction "OUT2B_20") (pintype "bidirectional"))
      (node (ref "U$4") (pin "21") (pinfunction "OUT2B_21") (pintype "bidirectional"))
      (node (ref "X6") (pin "2") (pinfunction "KL_2") (pintype "passive"))
    )
    (net (code "116") (name "Net-(X7A-KL)") (class "Default")
      (node (ref "U$5") (pin "2") (pinfunction "OUT1A_2") (pintype "bidirectional"))
      (node (ref "U$5") (pin "3") (pinfunction "OUT1A_3") (pintype "bidirectional"))
      (node (ref "X7") (pin "1") (pinfunction "KL_1") (pintype "passive"))
    )
    (net (code "117") (name "Net-(X7B-KL)") (class "Default")
      (node (ref "U$5") (pin "35") (pinfunction "OUT2A_35") (pintype "bidirectional"))
      (node (ref "U$5") (pin "36") (pinfunction "OUT2A_36") (pintype "bidirectional"))
      (node (ref "X7") (pin "2") (pinfunction "KL_2") (pintype "passive"))
    )
    (net (code "118") (name "Net-(X8A-KL)") (class "Default")
      (node (ref "U$5") (pin "17") (pinfunction "OUT1B_17") (pintype "bidirectional"))
      (node (ref "U$5") (pin "18") (pinfunction "OUT1B_18") (pintype "bidirectional"))
      (node (ref "X8") (pin "1") (pinfunction "KL_1") (pintype "passive"))
    )
    (net (code "119") (name "Net-(X8B-KL)") (class "Default")
      (node (ref "U$5") (pin "20") (pinfunction "OUT2B_20") (pintype "bidirectional"))
      (node (ref "U$5") (pin "21") (pinfunction "OUT2B_21") (pintype "bidirectional"))
      (node (ref "X8") (pin "2") (pinfunction "KL_2") (pintype "passive"))
    )
    (net (code "120") (name "Net-(X9A-KL)") (class "Default")
      (node (ref "U$6") (pin "2") (pinfunction "OUT1A_2") (pintype "bidirectional"))
      (node (ref "U$6") (pin "3") (pinfunction "OUT1A_3") (pintype "bidirectional"))
      (node (ref "X9") (pin "1") (pinfunction "KL_1") (pintype "passive"))
    )
    (net (code "121") (name "Net-(X9B-KL)") (class "Default")
      (node (ref "U$6") (pin "35") (pinfunction "OUT2A_35") (pintype "bidirectional"))
      (node (ref "U$6") (pin "36") (pinfunction "OUT2A_36") (pintype "bidirectional"))
      (node (ref "X9") (pin "2") (pinfunction "KL_2") (pintype "passive"))
    )
    (net (code "122") (name "Net-(X10A-KL)") (class "Default")
      (node (ref "U$6") (pin "17") (pinfunction "OUT1B_17") (pintype "bidirectional"))
      (node (ref "U$6") (pin "18") (pinfunction "OUT1B_18") (pintype "bidirectional"))
      (node (ref "X10") (pin "1") (pinfunction "KL_1") (pintype "passive"))
    )
    (net (code "123") (name "Net-(X10B-KL)") (class "Default")
      (node (ref "U$6") (pin "20") (pinfunction "OUT2B_20") (pintype "bidirectional"))
      (node (ref "U$6") (pin "21") (pinfunction "OUT2B_21") (pintype "bidirectional"))
      (node (ref "X10") (pin "2") (pinfunction "KL_2") (pintype "passive"))
    )
    (net (code "124") (name "Net-(X11A-KL)") (class "Default")
      (node (ref "U$7") (pin "2") (pinfunction "OUT1A_2") (pintype "bidirectional"))
      (node (ref "U$7") (pin "3") (pinfunction "OUT1A_3") (pintype "bidirectional"))
      (node (ref "X11") (pin "1") (pinfunction "KL_1") (pintype "passive"))
    )
    (net (code "125") (name "Net-(X11B-KL)") (class "Default")
      (node (ref "U$7") (pin "35") (pinfunction "OUT2A_35") (pintype "bidirectional"))
      (node (ref "U$7") (pin "36") (pinfunction "OUT2A_36") (pintype "bidirectional"))
      (node (ref "X11") (pin "2") (pinfunction "KL_2") (pintype "passive"))
    )
    (net (code "126") (name "Net-(X12A-KL)") (class "Default")
      (node (ref "U$7") (pin "17") (pinfunction "OUT1B_17") (pintype "bidirectional"))
      (node (ref "U$7") (pin "18") (pinfunction "OUT1B_18") (pintype "bidirectional"))
      (node (ref "X12") (pin "1") (pinfunction "KL_1") (pintype "passive"))
    )
    (net (code "127") (name "Net-(X12B-KL)") (class "Default")
      (node (ref "U$7") (pin "20") (pinfunction "OUT2B_20") (pintype "bidirectional"))
      (node (ref "U$7") (pin "21") (pinfunction "OUT2B_21") (pintype "bidirectional"))
      (node (ref "X12") (pin "2") (pinfunction "KL_2") (pintype "passive"))
    )
    (net (code "128") (name "Net-(X13A-KL)") (class "Default")
      (node (ref "U$8") (pin "2") (pinfunction "OUT1A_2") (pintype "bidirectional"))
      (node (ref "U$8") (pin "3") (pinfunction "OUT1A_3") (pintype "bidirectional"))
      (node (ref "X13") (pin "1") (pinfunction "KL_1") (pintype "passive"))
    )
    (net (code "129") (name "Net-(X13B-KL)") (class "Default")
      (node (ref "U$8") (pin "35") (pinfunction "OUT2A_35") (pintype "bidirectional"))
      (node (ref "U$8") (pin "36") (pinfunction "OUT2A_36") (pintype "bidirectional"))
      (node (ref "X13") (pin "2") (pinfunction "KL_2") (pintype "passive"))
    )
    (net (code "130") (name "Net-(X14A-KL)") (class "Default")
      (node (ref "U$8") (pin "17") (pinfunction "OUT1B_17") (pintype "bidirectional"))
      (node (ref "U$8") (pin "18") (pinfunction "OUT1B_18") (pintype "bidirectional"))
      (node (ref "X14") (pin "1") (pinfunction "KL_1") (pintype "passive"))
    )
    (net (code "131") (name "Net-(X14B-KL)") (class "Default")
      (node (ref "U$8") (pin "20") (pinfunction "OUT2B_20") (pintype "bidirectional"))
      (node (ref "U$8") (pin "21") (pinfunction "OUT2B_21") (pintype "bidirectional"))
      (node (ref "X14") (pin "2") (pinfunction "KL_2") (pintype "passive"))
    )
    (net (code "132") (name "Net-(X17A-KL)") (class "Default")
      (node (ref "R26") (pin "1") (pinfunction "1_1") (pintype "passive"))
      (node (ref "R6") (pin "1") (pinfunction "1_1") (pintype "passive"))
      (node (ref "X17") (pin "1") (pinfunction "KL_1") (pintype "passive"))
    )
    (net (code "133") (name "Net-(X18A-KL)") (class "Default")
      (node (ref "R11") (pin "1") (pinfunction "1_1") (pintype "passive"))
      (node (ref "R9") (pin "1") (pinfunction "1_1") (pintype "passive"))
      (node (ref "X18") (pin "1") (pinfunction "KL_1") (pintype "passive"))
    )
    (net (code "134") (name "Net-(X19A-KL)") (class "Default")
      (node (ref "R12") (pin "1") (pinfunction "1_1") (pintype "passive"))
      (node (ref "R14") (pin "1") (pinfunction "1_1") (pintype "passive"))
      (node (ref "X19") (pin "1") (pinfunction "KL_1") (pintype "passive"))
    )
    (net (code "135") (name "Net-(X20A-KL)") (class "Default")
      (node (ref "R15") (pin "1") (pinfunction "1_1") (pintype "passive"))
      (node (ref "R17") (pin "1") (pinfunction "1_1") (pintype "passive"))
      (node (ref "X20") (pin "1") (pinfunction "KL_1") (pintype "passive"))
    )
    (net (code "136") (name "Net-(X21A-KL)") (class "Default")
      (node (ref "R18") (pin "1") (pinfunction "1_1") (pintype "passive"))
      (node (ref "R20") (pin "1") (pinfunction "1_1") (pintype "passive"))
      (node (ref "X21") (pin "1") (pinfunction "KL_1") (pintype "passive"))
    )
    (net (code "137") (name "Net-(X22A-KL)") (class "Default")
      (node (ref "R21") (pin "1") (pinfunction "1_1") (pintype "passive"))
      (node (ref "R23") (pin "1") (pinfunction "1_1") (pintype "passive"))
      (node (ref "X22") (pin "1") (pinfunction "KL_1") (pintype "passive"))
    )
    (net (code "138") (name "Net-(X23A-KL)") (class "Default")
      (node (ref "R24") (pin "1") (pinfunction "1_1") (pintype "passive"))
      (node (ref "R28") (pin "1") (pinfunction "1_1") (pintype "passive"))
      (node (ref "X23") (pin "1") (pinfunction "KL_1") (pintype "passive"))
    )
    (net (code "139") (name "Net-(X24A-KL)") (class "Default")
      (node (ref "R29") (pin "1") (pinfunction "1_1") (pintype "passive"))
      (node (ref "R31") (pin "1") (pinfunction "1_1") (pintype "passive"))
      (node (ref "X24") (pin "1") (pinfunction "KL_1") (pintype "passive"))
    )
    (net (code "140") (name "Net-(X25A-KL)") (class "Default")
      (node (ref "R32") (pin "1") (pinfunction "1_1") (pintype "passive"))
      (node (ref "R34") (pin "1") (pinfunction "1_1") (pintype "passive"))
      (node (ref "X25") (pin "1") (pinfunction "KL_1") (pintype "passive"))
    )
    (net (code "141") (name "Net-(X26A-KL)") (class "Default")
      (node (ref "R35") (pin "1") (pinfunction "1_1") (pintype "passive"))
      (node (ref "R37") (pin "1") (pinfunction "1_1") (pintype "passive"))
      (node (ref "X26") (pin "1") (pinfunction "KL_1") (pintype "passive"))
    )
    (net (code "142") (name "Net-(X27-CR)") (class "Default")
      (node (ref "C54") (pin "1") (pinfunction "1_1") (pintype "passive"))
      (node (ref "R58") (pin "1") (pinfunction "1_1") (pintype "passive"))
      (node (ref "R59") (pin "2") (pinfunction "2_2") (pintype "passive"))
      (node (ref "X27") (pin "6") (pinfunction "CR_6") (pintype "input"))
    )
    (net (code "143") (name "Net-(X27-CT)") (class "Default")
      (node (ref "R60") (pin "1") (pinfunction "1_1") (pintype "passive"))
      (node (ref "X27") (pin "3") (pinfunction "CT_3") (pintype "input"))
    )
    (net (code "144") (name "RXN") (class "Default")
      (node (ref "R59") (pin "1") (pinfunction "1_1") (pintype "passive"))
      (node (ref "U$19") (pin "5") (pinfunction "RXN_5") (pintype "bidirectional"))
      (node (ref "X27") (pin "8") (pinfunction "RD-_8") (pintype "input"))
    )
    (net (code "145") (name "RXP") (class "Default")
      (node (ref "R58") (pin "2") (pinfunction "2_2") (pintype "passive"))
      (node (ref "U$19") (pin "6") (pinfunction "RXP_6") (pintype "bidirectional"))
      (node (ref "X27") (pin "7") (pinfunction "RD+_7") (pintype "input"))
    )
    (net (code "146") (name "SPDLED") (class "Default")
      (node (ref "R49") (pin "1") (pinfunction "1_1") (pintype "passive"))
      (node (ref "U$19") (pin "24") (pinfunction "SPDLED_24") (pintype "bidirectional"))
    )
    (net (code "147") (name "SPI_CHAIN") (class "Default")
      (node (ref "U$5") (pin "25") (pinfunction "SDO_25") (pintype "bidirectional"))
      (node (ref "U$6") (pin "27") (pinfunction "SDI_27") (pintype "bidirectional"))
    )
    (net (code "148") (name "SPI_CLK") (class "Default")
      (node (ref "U$2") (pin "19") (pinfunction "PA2/SSI0CLK_19") (pintype "bidirectional"))
      (node (ref "U$3") (pin "26") (pinfunction "CK_26") (pintype "bidirectional"))
      (node (ref "U$4") (pin "26") (pinfunction "CK_26") (pintype "bidirectional"))
      (node (ref "U$5") (pin "26") (pinfunction "CK_26") (pintype "bidirectional"))
      (node (ref "U$6") (pin "26") (pinfunction "CK_26") (pintype "bidirectional"))
      (node (ref "U$7") (pin "26") (pinfunction "CK_26") (pintype "bidirectional"))
      (node (ref "U$8") (pin "26") (pinfunction "CK_26") (pintype "bidirectional"))
    )
    (net (code "149") (name "SPI_SDI") (class "Default")
      (node (ref "U$2") (pin "22") (pinfunction "PA5/SSI0TX_22") (pintype "bidirectional"))
      (node (ref "U$3") (pin "27") (pinfunction "SDI_27") (pintype "bidirectional"))
    )
    (net (code "150") (name "SPI_SDO") (class "Default")
      (node (ref "U$2") (pin "21") (pinfunction "PA4/SSI0RX_21") (pintype "bidirectional"))
      (node (ref "U$8") (pin "25") (pinfunction "SDO_25") (pintype "bidirectional"))
    )
    (net (code "151") (name "TXN") (class "Default")
      (node (ref "R57") (pin "1") (pinfunction "1_1") (pintype "passive"))
      (node (ref "U$19") (pin "1") (pinfunction "TXN_1") (pintype "bidirectional"))
      (node (ref "X27") (pin "2") (pinfunction "TD-_2") (pintype "input"))
    )
    (net (code "152") (name "TXP") (class "Default")
      (node (ref "R56") (pin "1") (pinfunction "1_1") (pintype "passive"))
      (node (ref "U$19") (pin "2") (pinfunction "TXP_2") (pintype "bidirectional"))
      (node (ref "X27") (pin "1") (pinfunction "TD+_1") (pintype "input"))
    )
    (net (code "153") (name "UART_ARM_RX") (class "Default")
      (node (ref "IC2") (pin "12") (pinfunction "R1OUT_12") (pintype "output"))
      (node (ref "U$2") (pin "17") (pinfunction "PA0/U0RX_17") (pintype "bidirectional"))
    )
    (net (code "154") (name "UART_ARM_TX") (class "Default")
      (node (ref "IC2") (pin "11") (pinfunction "T1IN_11") (pintype "input"))
      (node (ref "U$2") (pin "18") (pinfunction "PA1/U0TX_18") (pintype "bidirectional"))
    )
    (net (code "155") (name "UART_PC_RX") (class "Default")
      (node (ref "IC2") (pin "14") (pinfunction "T1OUT_14") (pintype "output"))
      (node (ref "X16") (pin "2") (pinfunction "F_2") (pintype "passive"))
    )
    (net (code "156") (name "UART_PC_TX") (class "Default")
      (node (ref "IC2") (pin "13") (pinfunction "R1IN_13") (pintype "input"))
      (node (ref "X16") (pin "3") (pinfunction "F_3") (pintype "passive"))
    )
    (net (code "157") (name "V+") (class "Default")
      (node (ref "C27") (pin "1") (pinfunction "1_1") (pintype "passive"))
      (node (ref "C29") (pin "1") (pinfunction "1_1") (pintype "passive"))
      (node (ref "C31") (pin "1") (pinfunction "1_1") (pintype "passive"))
      (node (ref "C33") (pin "1") (pinfunction "1_1") (pintype "passive"))
      (node (ref "C35") (pin "1") (pinfunction "1_1") (pintype "passive"))
      (node (ref "C37") (pin "1") (pinfunction "1_1") (pintype "passive"))
      (node (ref "D3") (pin "1") (pinfunction "A_1") (pintype "passive"))
      (node (ref "D4") (pin "1") (pinfunction "A_1") (pintype "passive"))
      (node (ref "D5") (pin "1") (pinfunction "A_1") (pintype "passive"))
      (node (ref "D6") (pin "1") (pinfunction "A_1") (pintype "passive"))
      (node (ref "D7") (pin "1") (pinfunction "A_1") (pintype "passive"))
      (node (ref "D8") (pin "1") (pinfunction "A_1") (pintype "passive"))
      (node (ref "U$3") (pin "15") (pinfunction "VSB_15") (pintype "bidirectional"))
      (node (ref "U$3") (pin "16") (pinfunction "VSB_16") (pintype "bidirectional"))
      (node (ref "U$3") (pin "22") (pinfunction "VSB2_22") (pintype "bidirectional"))
      (node (ref "U$3") (pin "23") (pinfunction "VSB2_23") (pintype "bidirectional"))
      (node (ref "U$3") (pin "33") (pinfunction "VSA2_33") (pintype "bidirectional"))
      (node (ref "U$3") (pin "34") (pinfunction "VSA2_34") (pintype "bidirectional"))
      (node (ref "U$3") (pin "4") (pinfunction "VSA_4") (pintype "bidirectional"))
      (node (ref "U$3") (pin "5") (pinfunction "VSA_5") (pintype "bidirectional"))
      (node (ref "U$4") (pin "15") (pinfunction "VSB_15") (pintype "bidirectional"))
      (node (ref "U$4") (pin "16") (pinfunction "VSB_16") (pintype "bidirectional"))
      (node (ref "U$4") (pin "22") (pinfunction "VSB2_22") (pintype "bidirectional"))
      (node (ref "U$4") (pin "23") (pinfunction "VSB2_23") (pintype "bidirectional"))
      (node (ref "U$4") (pin "33") (pinfunction "VSA2_33") (pintype "bidirectional"))
      (node (ref "U$4") (pin "34") (pinfunction "VSA2_34") (pintype "bidirectional"))
      (node (ref "U$4") (pin "4") (pinfunction "VSA_4") (pintype "bidirectional"))
      (node (ref "U$4") (pin "5") (pinfunction "VSA_5") (pintype "bidirectional"))
      (node (ref "U$5") (pin "15") (pinfunction "VSB_15") (pintype "bidirectional"))
      (node (ref "U$5") (pin "16") (pinfunction "VSB_16") (pintype "bidirectional"))
      (node (ref "U$5") (pin "22") (pinfunction "VSB2_22") (pintype "bidirectional"))
      (node (ref "U$5") (pin "23") (pinfunction "VSB2_23") (pintype "bidirectional"))
      (node (ref "U$5") (pin "33") (pinfunction "VSA2_33") (pintype "bidirectional"))
      (node (ref "U$5") (pin "34") (pinfunction "VSA2_34") (pintype "bidirectional"))
      (node (ref "U$5") (pin "4") (pinfunction "VSA_4") (pintype "bidirectional"))
      (node (ref "U$5") (pin "5") (pinfunction "VSA_5") (pintype "bidirectional"))
      (node (ref "U$6") (pin "15") (pinfunction "VSB_15") (pintype "bidirectional"))
      (node (ref "U$6") (pin "16") (pinfunction "VSB_16") (pintype "bidirectional"))
      (node (ref "U$6") (pin "22") (pinfunction "VSB2_22") (pintype "bidirectional"))
      (node (ref "U$6") (pin "23") (pinfunction "VSB2_23") (pintype "bidirectional"))
      (node (ref "U$6") (pin "33") (pinfunction "VSA2_33") (pintype "bidirectional"))
      (node (ref "U$6") (pin "34") (pinfunction "VSA2_34") (pintype "bidirectional"))
      (node (ref "U$6") (pin "4") (pinfunction "VSA_4") (pintype "bidirectional"))
      (node (ref "U$6") (pin "5") (pinfunction "VSA_5") (pintype "bidirectional"))
      (node (ref "U$7") (pin "15") (pinfunction "VSB_15") (pintype "bidirectional"))
      (node (ref "U$7") (pin "16") (pinfunction "VSB_16") (pintype "bidirectional"))
      (node (ref "U$7") (pin "22") (pinfunction "VSB2_22") (pintype "bidirectional"))
      (node (ref "U$7") (pin "23") (pinfunction "VSB2_23") (pintype "bidirectional"))
      (node (ref "U$7") (pin "33") (pinfunction "VSA2_33") (pintype "bidirectional"))
      (node (ref "U$7") (pin "34") (pinfunction "VSA2_34") (pintype "bidirectional"))
      (node (ref "U$7") (pin "4") (pinfunction "VSA_4") (pintype "bidirectional"))
      (node (ref "U$7") (pin "5") (pinfunction "VSA_5") (pintype "bidirectional"))
      (node (ref "U$8") (pin "15") (pinfunction "VSB_15") (pintype "bidirectional"))
      (node (ref "U$8") (pin "16") (pinfunction "VSB_16") (pintype "bidirectional"))
      (node (ref "U$8") (pin "22") (pinfunction "VSB2_22") (pintype "bidirectional"))
      (node (ref "U$8") (pin "23") (pinfunction "VSB2_23") (pintype "bidirectional"))
      (node (ref "U$8") (pin "33") (pinfunction "VSA2_33") (pintype "bidirectional"))
      (node (ref "U$8") (pin "34") (pinfunction "VSA2_34") (pintype "bidirectional"))
      (node (ref "U$8") (pin "4") (pinfunction "VSA_4") (pintype "bidirectional"))
      (node (ref "U$8") (pin "5") (pinfunction "VSA_5") (pintype "bidirectional"))
      (node (ref "X28") (pin "2") (pinfunction "KL_2") (pintype "passive"))
    )
    (net (code "158") (name "VCC") (class "Default")
      (node (ref "C14") (pin "1") (pinfunction "1_1") (pintype "passive"))
      (node (ref "C15") (pin "1") (pinfunction "1_1") (pintype "passive"))
      (node (ref "C16") (pin "1") (pinfunction "1_1") (pintype "passive"))
      (node (ref "C8") (pin "1") (pinfunction "1_1") (pintype "passive"))
      (node (ref "U$2") (pin "25") (pinfunction "VDDC_25") (pintype "bidirectional"))
      (node (ref "U$2") (pin "56") (pinfunction "VDDC_56") (pintype "bidirectional"))
    )
    (net (code "159") (name "unconnected-(IC2A-R2OUT-Pad9)") (class "Default")
      (node (ref "IC2") (pin "9") (pinfunction "R2OUT_9") (pintype "output"))
    )
    (net (code "160") (name "unconnected-(IC2A-T2OUT-Pad7)") (class "Default")
      (node (ref "IC2") (pin "7") (pinfunction "T2OUT_7") (pintype "output"))
    )
    (net (code "161") (name "unconnected-(U$1-~{SHDN}-Pad5)") (class "Default")
      (node (ref "U$1") (pin "5") (pinfunction "~{SHDN}_5") (pintype "bidirectional"))
    )
    (net (code "162") (name "unconnected-(U$2A-PB0-Pad45)") (class "Default")
      (node (ref "U$2") (pin "45") (pinfunction "PB0_45") (pintype "bidirectional"))
    )
    (net (code "163") (name "unconnected-(U$2A-PB1-Pad46)") (class "Default")
      (node (ref "U$2") (pin "46") (pinfunction "PB1_46") (pintype "bidirectional"))
    )
    (net (code "164") (name "unconnected-(U$2A-PB4-Pad58)") (class "Default")
      (node (ref "U$2") (pin "58") (pinfunction "PB4_58") (pintype "bidirectional"))
    )
    (net (code "165") (name "unconnected-(U$2A-PB5-Pad57)") (class "Default")
      (node (ref "U$2") (pin "57") (pinfunction "PB5_57") (pintype "bidirectional"))
    )
    (net (code "166") (name "unconnected-(U$2A-PD6-Pad53)") (class "Default")
      (node (ref "U$2") (pin "53") (pinfunction "PD6_53") (pintype "bidirectional"))
    )
    (net (code "167") (name "unconnected-(U$2A-XOSC1-Pad36)") (class "Default")
      (node (ref "U$2") (pin "36") (pinfunction "XOSC1_36") (pintype "bidirectional"))
    )
    (net (code "168") (name "unconnected-(U$2A-~{HIB}-Pad33)") (class "Default")
      (node (ref "U$2") (pin "33") (pinfunction "~{HIB}_33") (pintype "bidirectional"))
    )
    (net (code "169") (name "unconnected-(U$3-ADCIN-Pad8)") (class "Default")
      (node (ref "U$3") (pin "8") (pinfunction "ADCIN_8") (pintype "bidirectional"))
    )
    (net (code "170") (name "unconnected-(U$3-BUSYN{slash}SYNC-Pad29)") (class "Default")
      (node (ref "U$3") (pin "29") (pinfunction "BUSYN/SYNC_29") (pintype "bidirectional"))
    )
    (net (code "171") (name "unconnected-(U$3-OSCIN-Pad10)") (class "Default")
      (node (ref "U$3") (pin "10") (pinfunction "OSCIN_10") (pintype "bidirectional"))
    )
    (net (code "172") (name "unconnected-(U$3-OSCOUT-Pad11)") (class "Default")
      (node (ref "U$3") (pin "11") (pinfunction "OSCOUT_11") (pintype "bidirectional"))
    )
    (net (code "173") (name "unconnected-(U$3-STCK-Pad32)") (class "Default")
      (node (ref "U$3") (pin "32") (pinfunction "STCK_32") (pintype "bidirectional"))
    )
    (net (code "174") (name "unconnected-(U$4-ADCIN-Pad8)") (class "Default")
      (node (ref "U$4") (pin "8") (pinfunction "ADCIN_8") (pintype "bidirectional"))
    )
    (net (code "175") (name "unconnected-(U$4-BUSYN{slash}SYNC-Pad29)") (class "Default")
      (node (ref "U$4") (pin "29") (pinfunction "BUSYN/SYNC_29") (pintype "bidirectional"))
    )
    (net (code "176") (name "unconnected-(U$4-OSCIN-Pad10)") (class "Default")
      (node (ref "U$4") (pin "10") (pinfunction "OSCIN_10") (pintype "bidirectional"))
    )
    (net (code "177") (name "unconnected-(U$4-OSCOUT-Pad11)") (class "Default")
      (node (ref "U$4") (pin "11") (pinfunction "OSCOUT_11") (pintype "bidirectional"))
    )
    (net (code "178") (name "unconnected-(U$4-STCK-Pad32)") (class "Default")
      (node (ref "U$4") (pin "32") (pinfunction "STCK_32") (pintype "bidirectional"))
    )
    (net (code "179") (name "unconnected-(U$5-ADCIN-Pad8)") (class "Default")
      (node (ref "U$5") (pin "8") (pinfunction "ADCIN_8") (pintype "bidirectional"))
    )
    (net (code "180") (name "unconnected-(U$5-BUSYN{slash}SYNC-Pad29)") (class "Default")
      (node (ref "U$5") (pin "29") (pinfunction "BUSYN/SYNC_29") (pintype "bidirectional"))
    )
    (net (code "181") (name "unconnected-(U$5-OSCIN-Pad10)") (class "Default")
      (node (ref "U$5") (pin "10") (pinfunction "OSCIN_10") (pintype "bidirectional"))
    )
    (net (code "182") (name "unconnected-(U$5-OSCOUT-Pad11)") (class "Default")
      (node (ref "U$5") (pin "11") (pinfunction "OSCOUT_11") (pintype "bidirectional"))
    )
    (net (code "183") (name "unconnected-(U$5-STCK-Pad32)") (class "Default")
      (node (ref "U$5") (pin "32") (pinfunction "STCK_32") (pintype "bidirectional"))
    )
    (net (code "184") (name "unconnected-(U$6-ADCIN-Pad8)") (class "Default")
      (node (ref "U$6") (pin "8") (pinfunction "ADCIN_8") (pintype "bidirectional"))
    )
    (net (code "185") (name "unconnected-(U$6-BUSYN{slash}SYNC-Pad29)") (class "Default")
      (node (ref "U$6") (pin "29") (pinfunction "BUSYN/SYNC_29") (pintype "bidirectional"))
    )
    (net (code "186") (name "unconnected-(U$6-OSCIN-Pad10)") (class "Default")
      (node (ref "U$6") (pin "10") (pinfunction "OSCIN_10") (pintype "bidirectional"))
    )
    (net (code "187") (name "unconnected-(U$6-OSCOUT-Pad11)") (class "Default")
      (node (ref "U$6") (pin "11") (pinfunction "OSCOUT_11") (pintype "bidirectional"))
    )
    (net (code "188") (name "unconnected-(U$6-STCK-Pad32)") (class "Default")
      (node (ref "U$6") (pin "32") (pinfunction "STCK_32") (pintype "bidirectional"))
    )
    (net (code "189") (name "unconnected-(U$7-ADCIN-Pad8)") (class "Default")
      (node (ref "U$7") (pin "8") (pinfunction "ADCIN_8") (pintype "bidirectional"))
    )
    (net (code "190") (name "unconnected-(U$7-BUSYN{slash}SYNC-Pad29)") (class "Default")
      (node (ref "U$7") (pin "29") (pinfunction "BUSYN/SYNC_29") (pintype "bidirectional"))
    )
    (net (code "191") (name "unconnected-(U$7-OSCIN-Pad10)") (class "Default")
      (node (ref "U$7") (pin "10") (pinfunction "OSCIN_10") (pintype "bidirectional"))
    )
    (net (code "192") (name "unconnected-(U$7-OSCOUT-Pad11)") (class "Default")
      (node (ref "U$7") (pin "11") (pinfunction "OSCOUT_11") (pintype "bidirectional"))
    )
    (net (code "193") (name "unconnected-(U$7-STCK-Pad32)") (class "Default")
      (node (ref "U$7") (pin "32") (pinfunction "STCK_32") (pintype "bidirectional"))
    )
    (net (code "194") (name "unconnected-(U$8-ADCIN-Pad8)") (class "Default")
      (node (ref "U$8") (pin "8") (pinfunction "ADCIN_8") (pintype "bidirectional"))
    )
    (net (code "195") (name "unconnected-(U$8-BUSYN{slash}SYNC-Pad29)") (class "Default")
      (node (ref "U$8") (pin "29") (pinfunction "BUSYN/SYNC_29") (pintype "bidirectional"))
    )
    (net (code "196") (name "unconnected-(U$8-OSCIN-Pad10)") (class "Default")
      (node (ref "U$8") (pin "10") (pinfunction "OSCIN_10") (pintype "bidirectional"))
    )
    (net (code "197") (name "unconnected-(U$8-OSCOUT-Pad11)") (class "Default")
      (node (ref "U$8") (pin "11") (pinfunction "OSCOUT_11") (pintype "bidirectional"))
    )
    (net (code "198") (name "unconnected-(U$8-STCK-Pad32)") (class "Default")
      (node (ref "U$8") (pin "32") (pinfunction "STCK_32") (pintype "bidirectional"))
    )
    (net (code "199") (name "unconnected-(U$9-BAS-Pad7)") (class "Default")
      (node (ref "U$9") (pin "7") (pinfunction "BAS_7") (pintype "passive"))
    )
    (net (code "200") (name "unconnected-(U$10-BAS-Pad7)") (class "Default")
      (node (ref "U$10") (pin "7") (pinfunction "BAS_7") (pintype "passive"))
    )
    (net (code "201") (name "unconnected-(U$11-BAS-Pad7)") (class "Default")
      (node (ref "U$11") (pin "7") (pinfunction "BAS_7") (pintype "passive"))
    )
    (net (code "202") (name "unconnected-(U$12-BAS-Pad7)") (class "Default")
      (node (ref "U$12") (pin "7") (pinfunction "BAS_7") (pintype "passive"))
    )
    (net (code "203") (name "unconnected-(U$13-BAS-Pad7)") (class "Default")
      (node (ref "U$13") (pin "7") (pinfunction "BAS_7") (pintype "passive"))
    )
    (net (code "204") (name "unconnected-(U$14-BAS-Pad7)") (class "Default")
      (node (ref "U$14") (pin "7") (pinfunction "BAS_7") (pintype "passive"))
    )
    (net (code "205") (name "unconnected-(U$15-BAS-Pad7)") (class "Default")
      (node (ref "U$15") (pin "7") (pinfunction "BAS_7") (pintype "passive"))
    )
    (net (code "206") (name "unconnected-(U$16-BAS-Pad7)") (class "Default")
      (node (ref "U$16") (pin "7") (pinfunction "BAS_7") (pintype "passive"))
    )
    (net (code "207") (name "unconnected-(U$17-BAS-Pad7)") (class "Default")
      (node (ref "U$17") (pin "7") (pinfunction "BAS_7") (pintype "passive"))
    )
    (net (code "208") (name "unconnected-(U$18-BAS-Pad7)") (class "Default")
      (node (ref "U$18") (pin "7") (pinfunction "BAS_7") (pintype "passive"))
    )
    (net (code "209") (name "unconnected-(U$19A-1V2O-Pad22)") (class "Default")
      (node (ref "U$19") (pin "22") (pinfunction "1V2O_22") (pintype "bidirectional"))
    )
    (net (code "210") (name "unconnected-(U$19A-DNC-Pad7)") (class "Default")
      (node (ref "U$19") (pin "7") (pinfunction "DNC_7") (pintype "bidirectional"))
    )
    (net (code "211") (name "unconnected-(U$19A-DUPLED-Pad26)") (class "Default")
      (node (ref "U$19") (pin "26") (pinfunction "DUPLED_26") (pintype "bidirectional"))
    )
    (net (code "212") (name "unconnected-(U$19A-VBG-Pad18)") (class "Default")
      (node (ref "U$19") (pin "18") (pinfunction "VBG_18") (pintype "bidirectional"))
    )
    (net (code "213") (name "unconnected-(U$24-BAS-Pad7)") (class "Default")
      (node (ref "U$24") (pin "7") (pinfunction "BAS_7") (pintype "passive"))
    )
    (net (code "214") (name "unconnected-(X16-PadG2)") (class "Default")
      (node (ref "X16") (pin "G2") (pinfunction "G2_G2") (pintype "passive"))
    )
    (net (code "215") (name "unconnected-(X16A-F-Pad1)") (class "Default")
      (node (ref "X16") (pin "1") (pinfunction "F_1") (pintype "passive"))
    )
    (net (code "216") (name "unconnected-(X16D-F-Pad4)") (class "Default")
      (node (ref "X16") (pin "4") (pinfunction "F_4") (pintype "passive"))
    )
    (net (code "217") (name "unconnected-(X16E-F-Pad5)") (class "Default")
      (node (ref "X16") (pin "5") (pinfunction "F_5") (pintype "passive"))
    )
    (net (code "218") (name "unconnected-(X16F-F-Pad6)") (class "Default")
      (node (ref "X16") (pin "6") (pinfunction "F_6") (pintype "passive"))
    )
    (net (code "219") (name "unconnected-(X16G-F-Pad7)") (class "Default")
      (node (ref "X16") (pin "7") (pinfunction "F_7") (pintype "passive"))
    )
    (net (code "220") (name "unconnected-(X16H-F-Pad8)") (class "Default")
      (node (ref "X16") (pin "8") (pinfunction "F_8") (pintype "passive"))
    )
    (net (code "221") (name "unconnected-(X16I-F-Pad9)") (class "Default")
      (node (ref "X16") (pin "9") (pinfunction "F_9") (pintype "passive"))
    )
    (net (code "222") (name "unconnected-(X27-NC{slash}4-Pad4)") (class "Default")
      (node (ref "X27") (pin "4") (pinfunction "NC/4_4") (pintype "input"))
    )
    (net (code "223") (name "unconnected-(X27-NC{slash}5-Pad5)") (class "Default")
      (node (ref "X27") (pin "5") (pinfunction "NC/5_5") (pintype "input"))
    )
    (net (code "224") (name "~{MOT0_FLAG}") (class "Default")
      (node (ref "U$2") (pin "24") (pinfunction "PA7_24") (pintype "bidirectional"))
      (node (ref "U$3") (pin "31") (pinfunction "FLAGN_31") (pintype "bidirectional"))
    )
    (net (code "225") (name "~{MOT1_FLAG}") (class "Default")
      (node (ref "U$2") (pin "23") (pinfunction "PA6_23") (pintype "bidirectional"))
      (node (ref "U$4") (pin "31") (pinfunction "FLAGN_31") (pintype "bidirectional"))
    )
    (net (code "226") (name "~{MOT2_FLAG}") (class "Default")
      (node (ref "U$2") (pin "16") (pinfunction "PC4_16") (pintype "bidirectional"))
      (node (ref "U$5") (pin "31") (pinfunction "FLAGN_31") (pintype "bidirectional"))
    )
    (net (code "227") (name "~{MOT3_FLAG}") (class "Default")
      (node (ref "U$2") (pin "15") (pinfunction "PC5_15") (pintype "bidirectional"))
      (node (ref "U$6") (pin "31") (pinfunction "FLAGN_31") (pintype "bidirectional"))
    )
    (net (code "228") (name "~{MOT4_FLAG}") (class "Default")
      (node (ref "U$2") (pin "60") (pinfunction "PE5_60") (pintype "bidirectional"))
      (node (ref "U$7") (pin "31") (pinfunction "FLAGN_31") (pintype "bidirectional"))
    )
    (net (code "229") (name "~{MOT5_FLAG}") (class "Default")
      (node (ref "U$2") (pin "59") (pinfunction "PE4_59") (pintype "bidirectional"))
      (node (ref "U$8") (pin "31") (pinfunction "FLAGN_31") (pintype "bidirectional"))
    )
    (net (code "230") (name "~{MOT_RESET}") (class "Default")
      (node (ref "U$2") (pin "44") (pinfunction "PD5_44") (pintype "bidirectional"))
      (node (ref "U$3") (pin "6") (pinfunction "STBYN/RESETN_6") (pintype "bidirectional"))
      (node (ref "U$4") (pin "6") (pinfunction "STBYN/RESETN_6") (pintype "bidirectional"))
      (node (ref "U$5") (pin "6") (pinfunction "STBYN/RESETN_6") (pintype "bidirectional"))
      (node (ref "U$6") (pin "6") (pinfunction "STBYN/RESETN_6") (pintype "bidirectional"))
      (node (ref "U$7") (pin "6") (pinfunction "STBYN/RESETN_6") (pintype "bidirectional"))
      (node (ref "U$8") (pin "6") (pinfunction "STBYN/RESETN_6") (pintype "bidirectional"))
    )
    (net (code "231") (name "~{SPI_CS}") (class "Default")
      (node (ref "U$2") (pin "20") (pinfunction "PA3/SSI0FSS_20") (pintype "bidirectional"))
      (node (ref "U$3") (pin "30") (pinfunction "CSN_30") (pintype "bidirectional"))
      (node (ref "U$4") (pin "30") (pinfunction "CSN_30") (pintype "bidirectional"))
      (node (ref "U$5") (pin "30") (pinfunction "CSN_30") (pintype "bidirectional"))
      (node (ref "U$6") (pin "30") (pinfunction "CSN_30") (pintype "bidirectional"))
      (node (ref "U$7") (pin "30") (pinfunction "CSN_30") (pintype "bidirectional"))
      (node (ref "U$8") (pin "30") (pinfunction "CSN_30") (pintype "bidirectional"))
    )
  )
)
